# M7104B.net
KiCad netlist of a schematic drawn in EAGLE
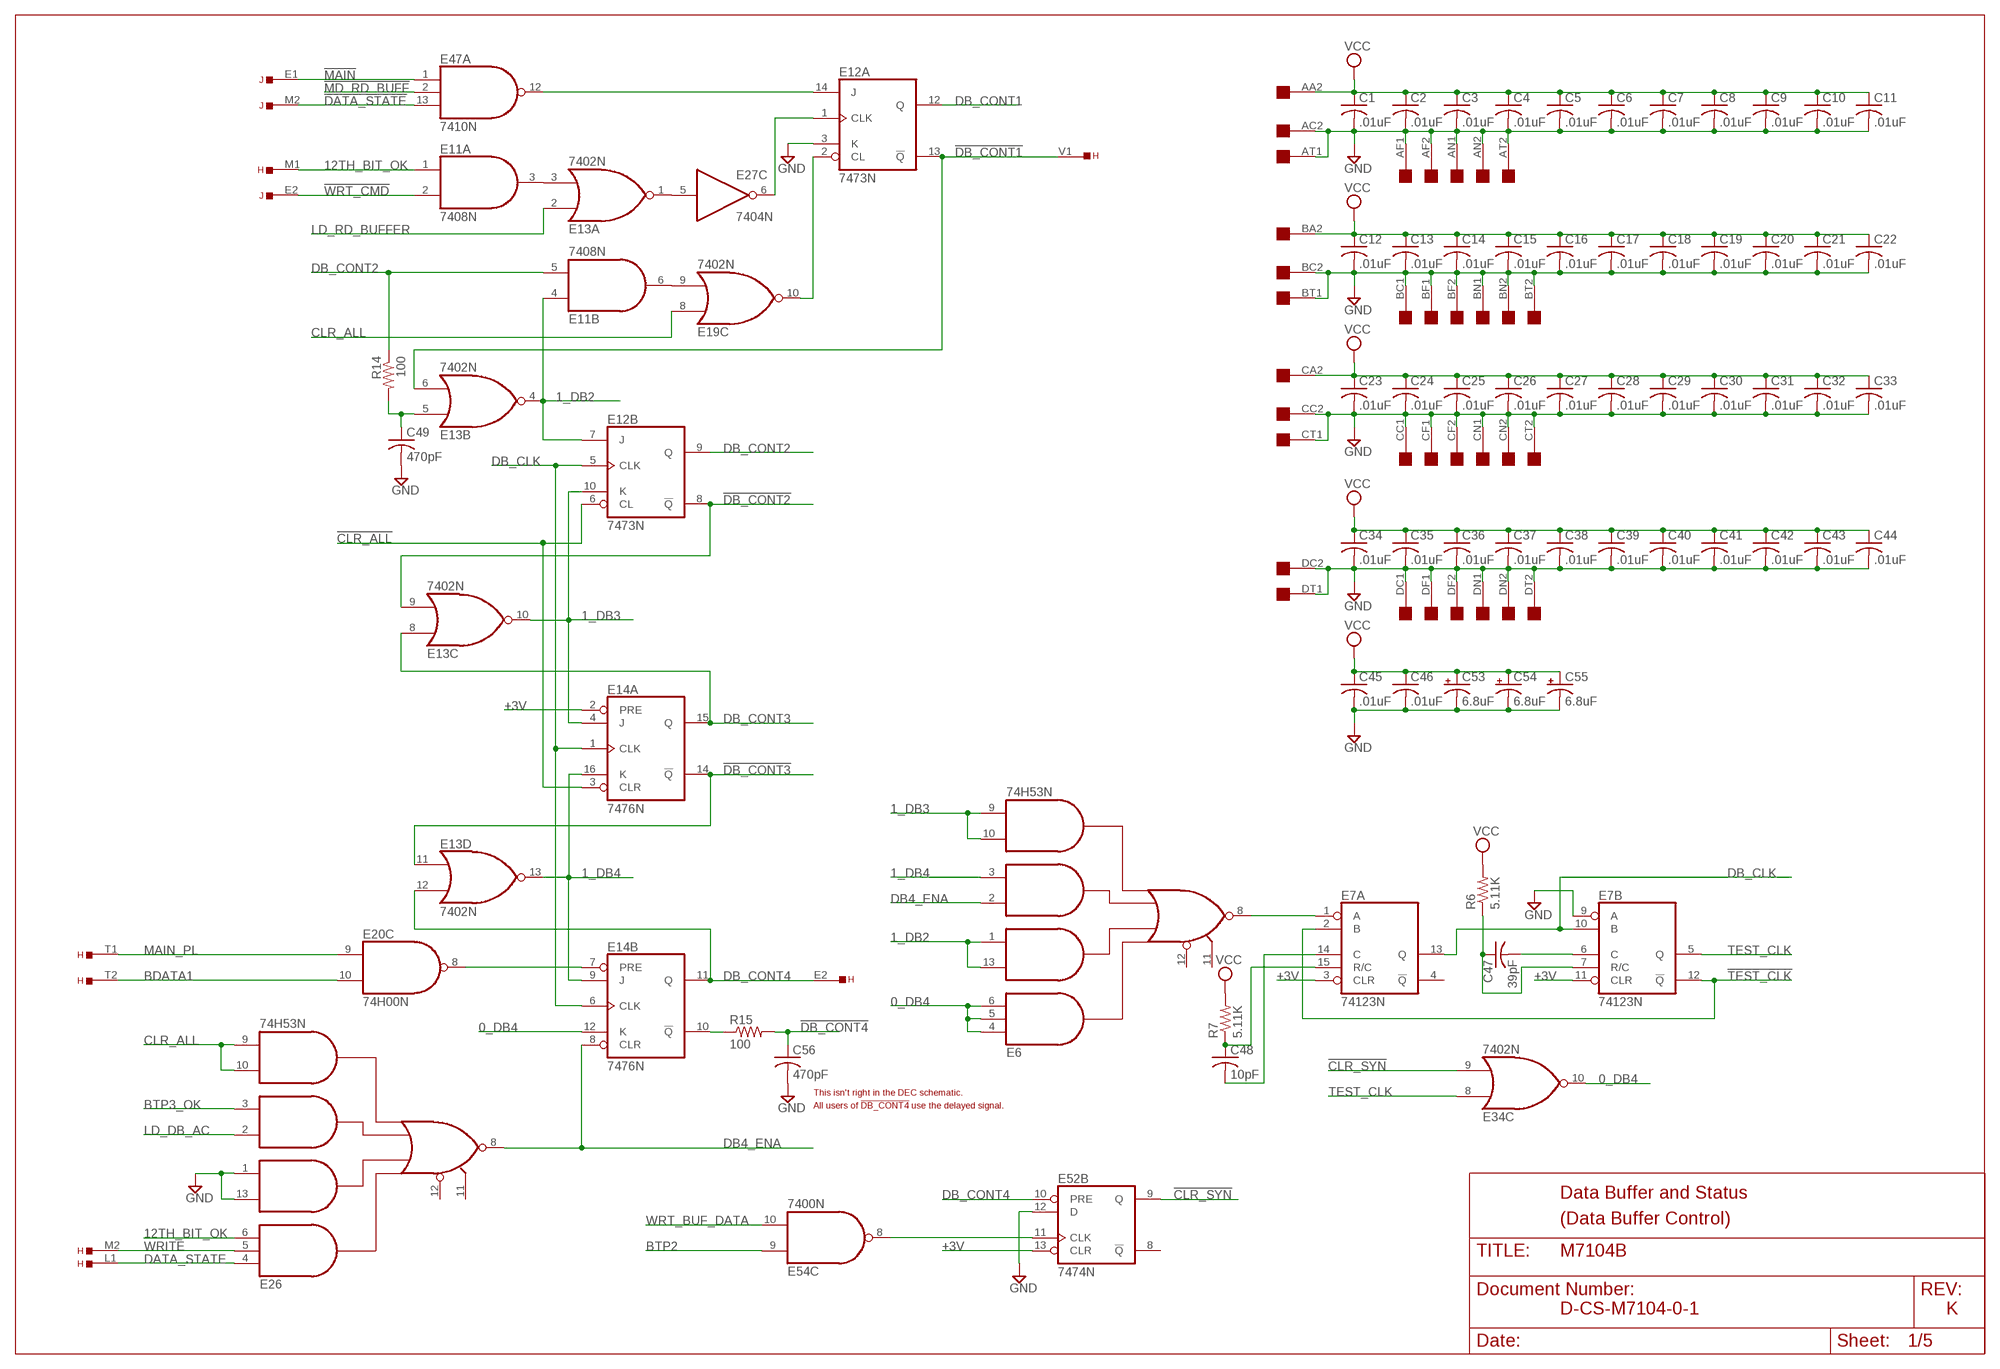
[diagram p0: schematic, sheet 1]
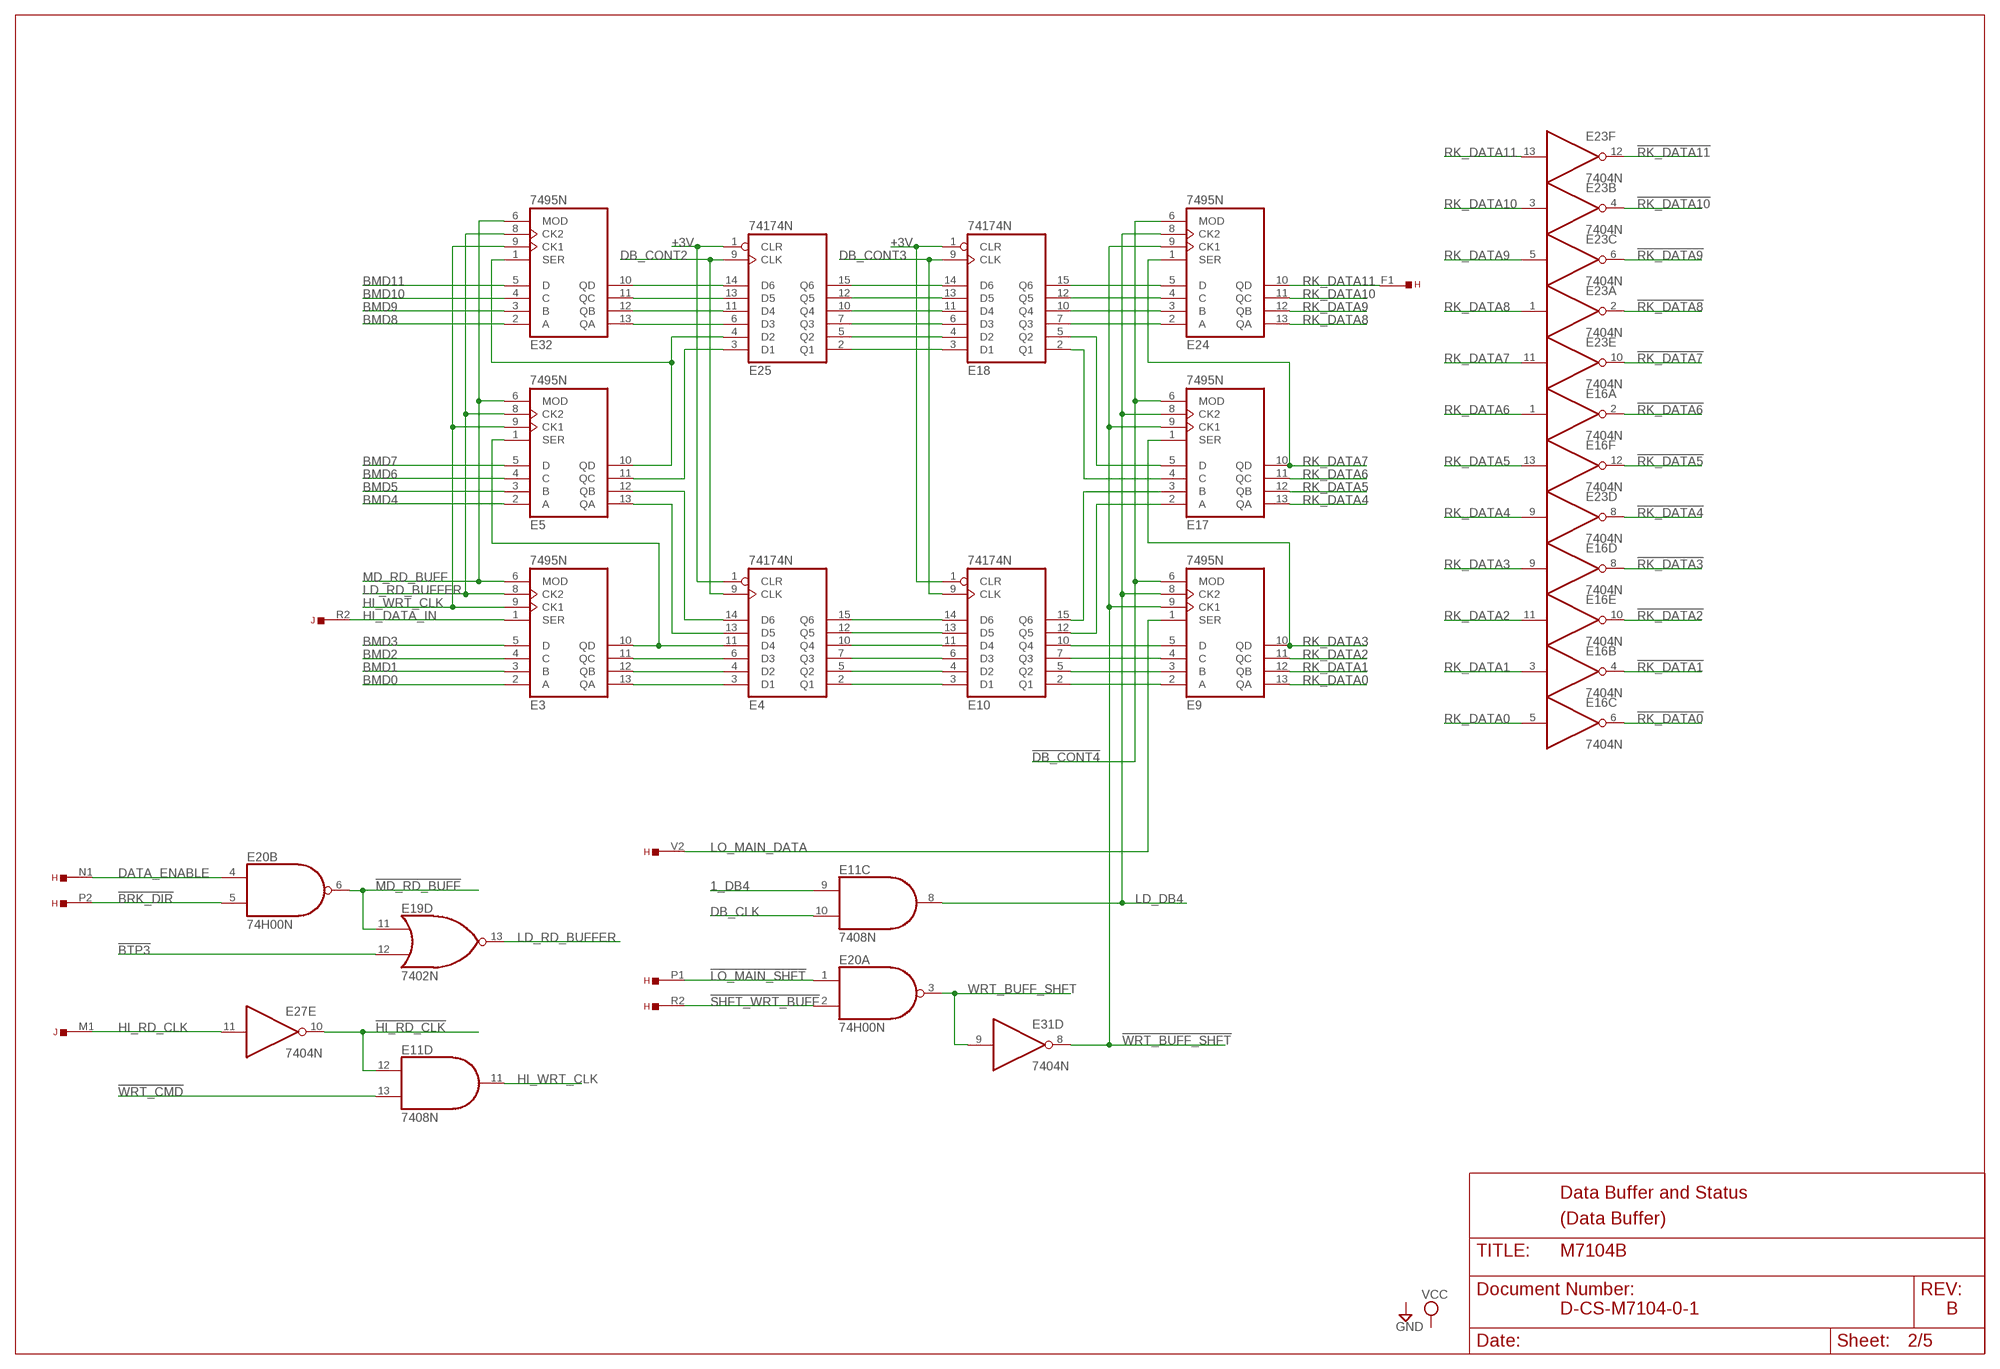
[diagram p1: schematic, sheet 2]
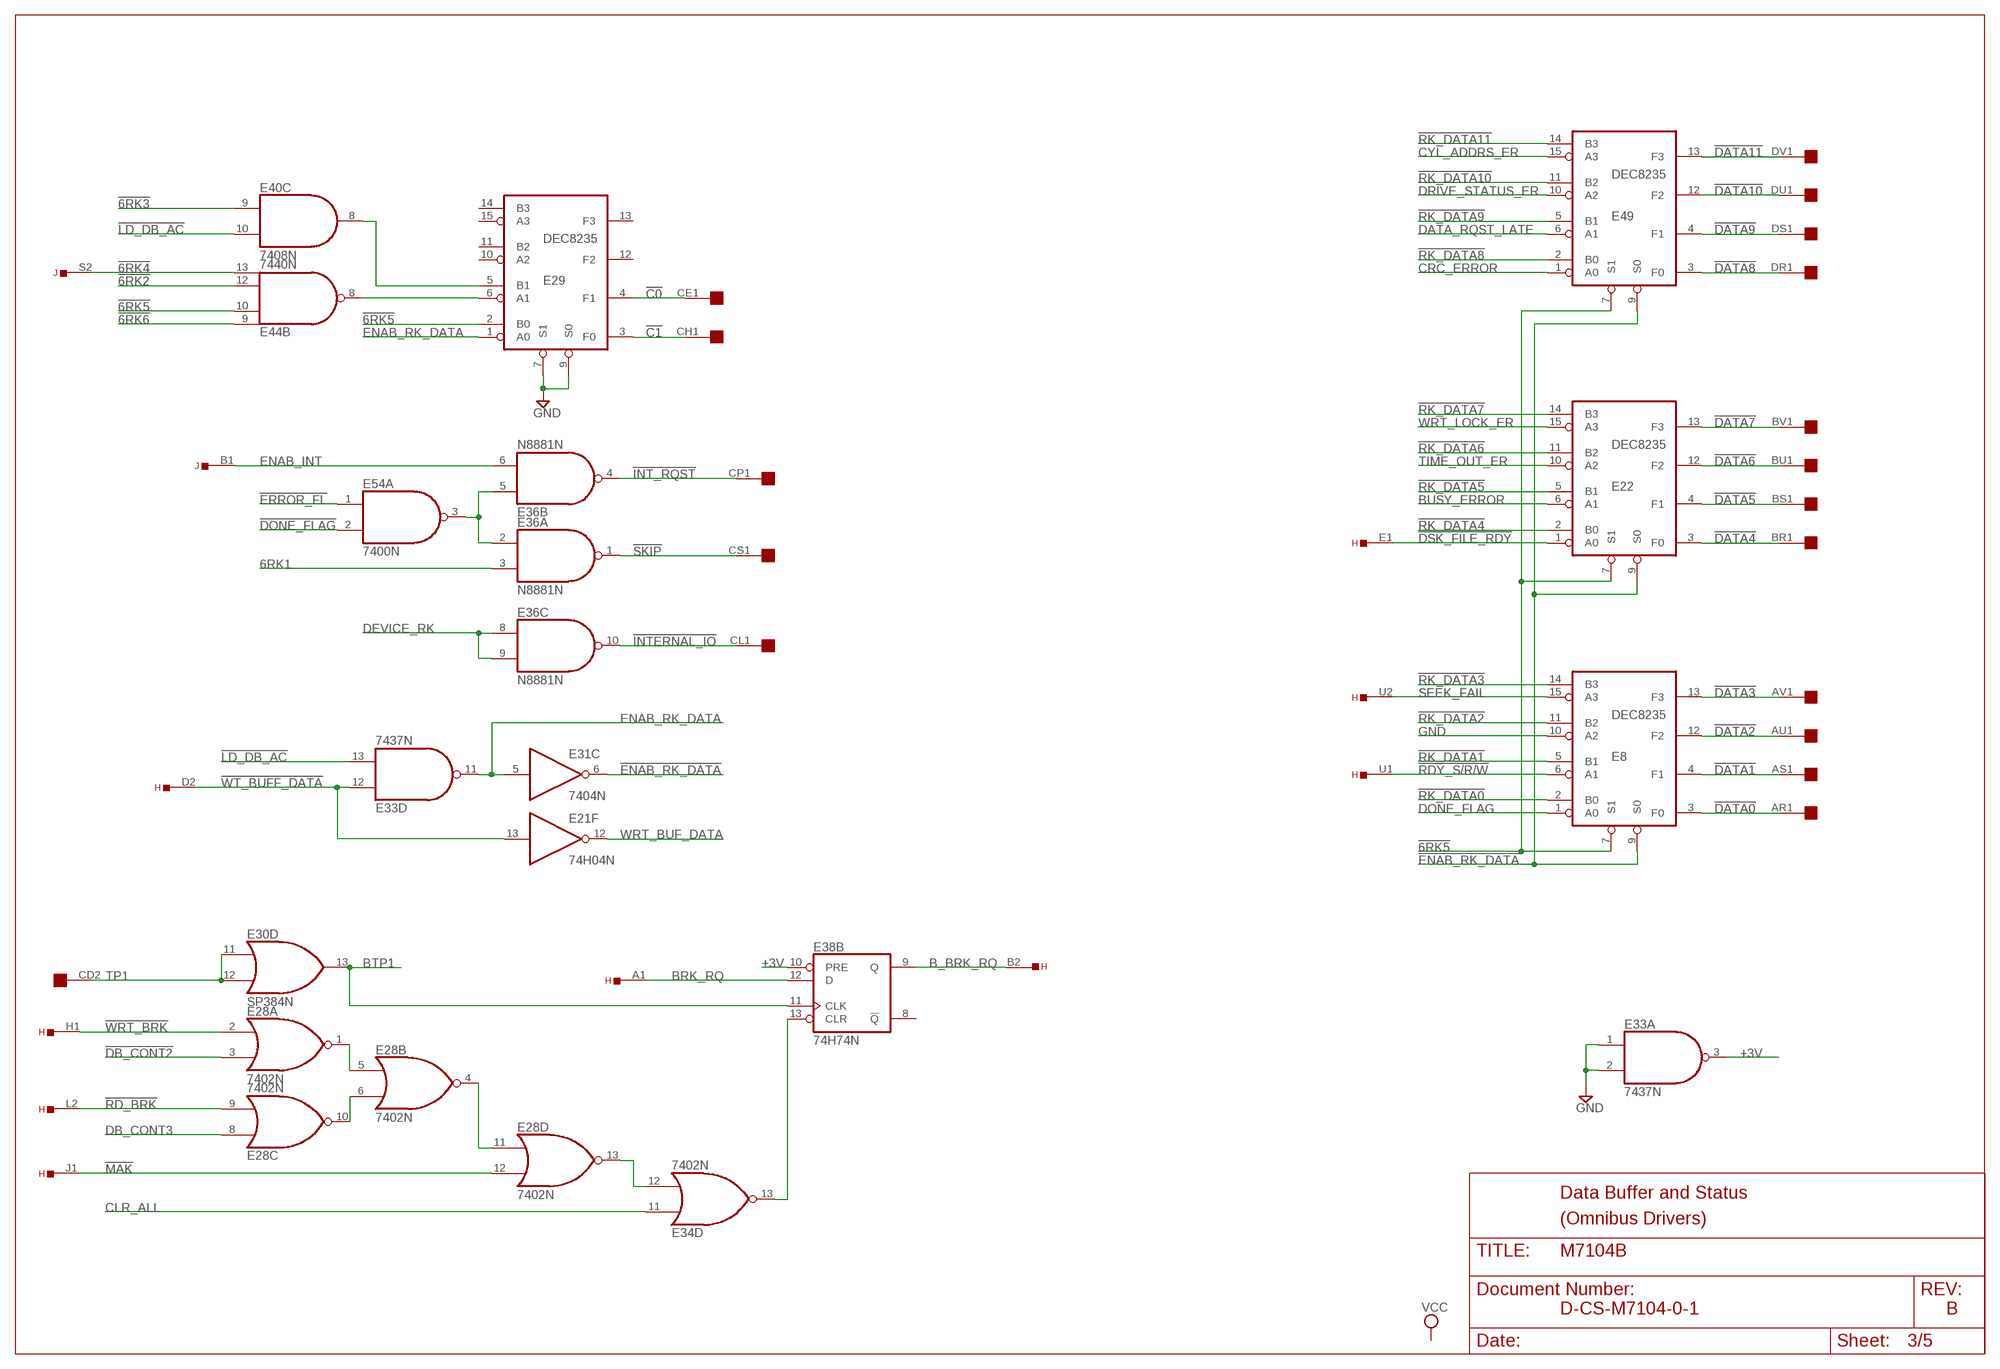
[diagram p2: schematic, sheet 3]
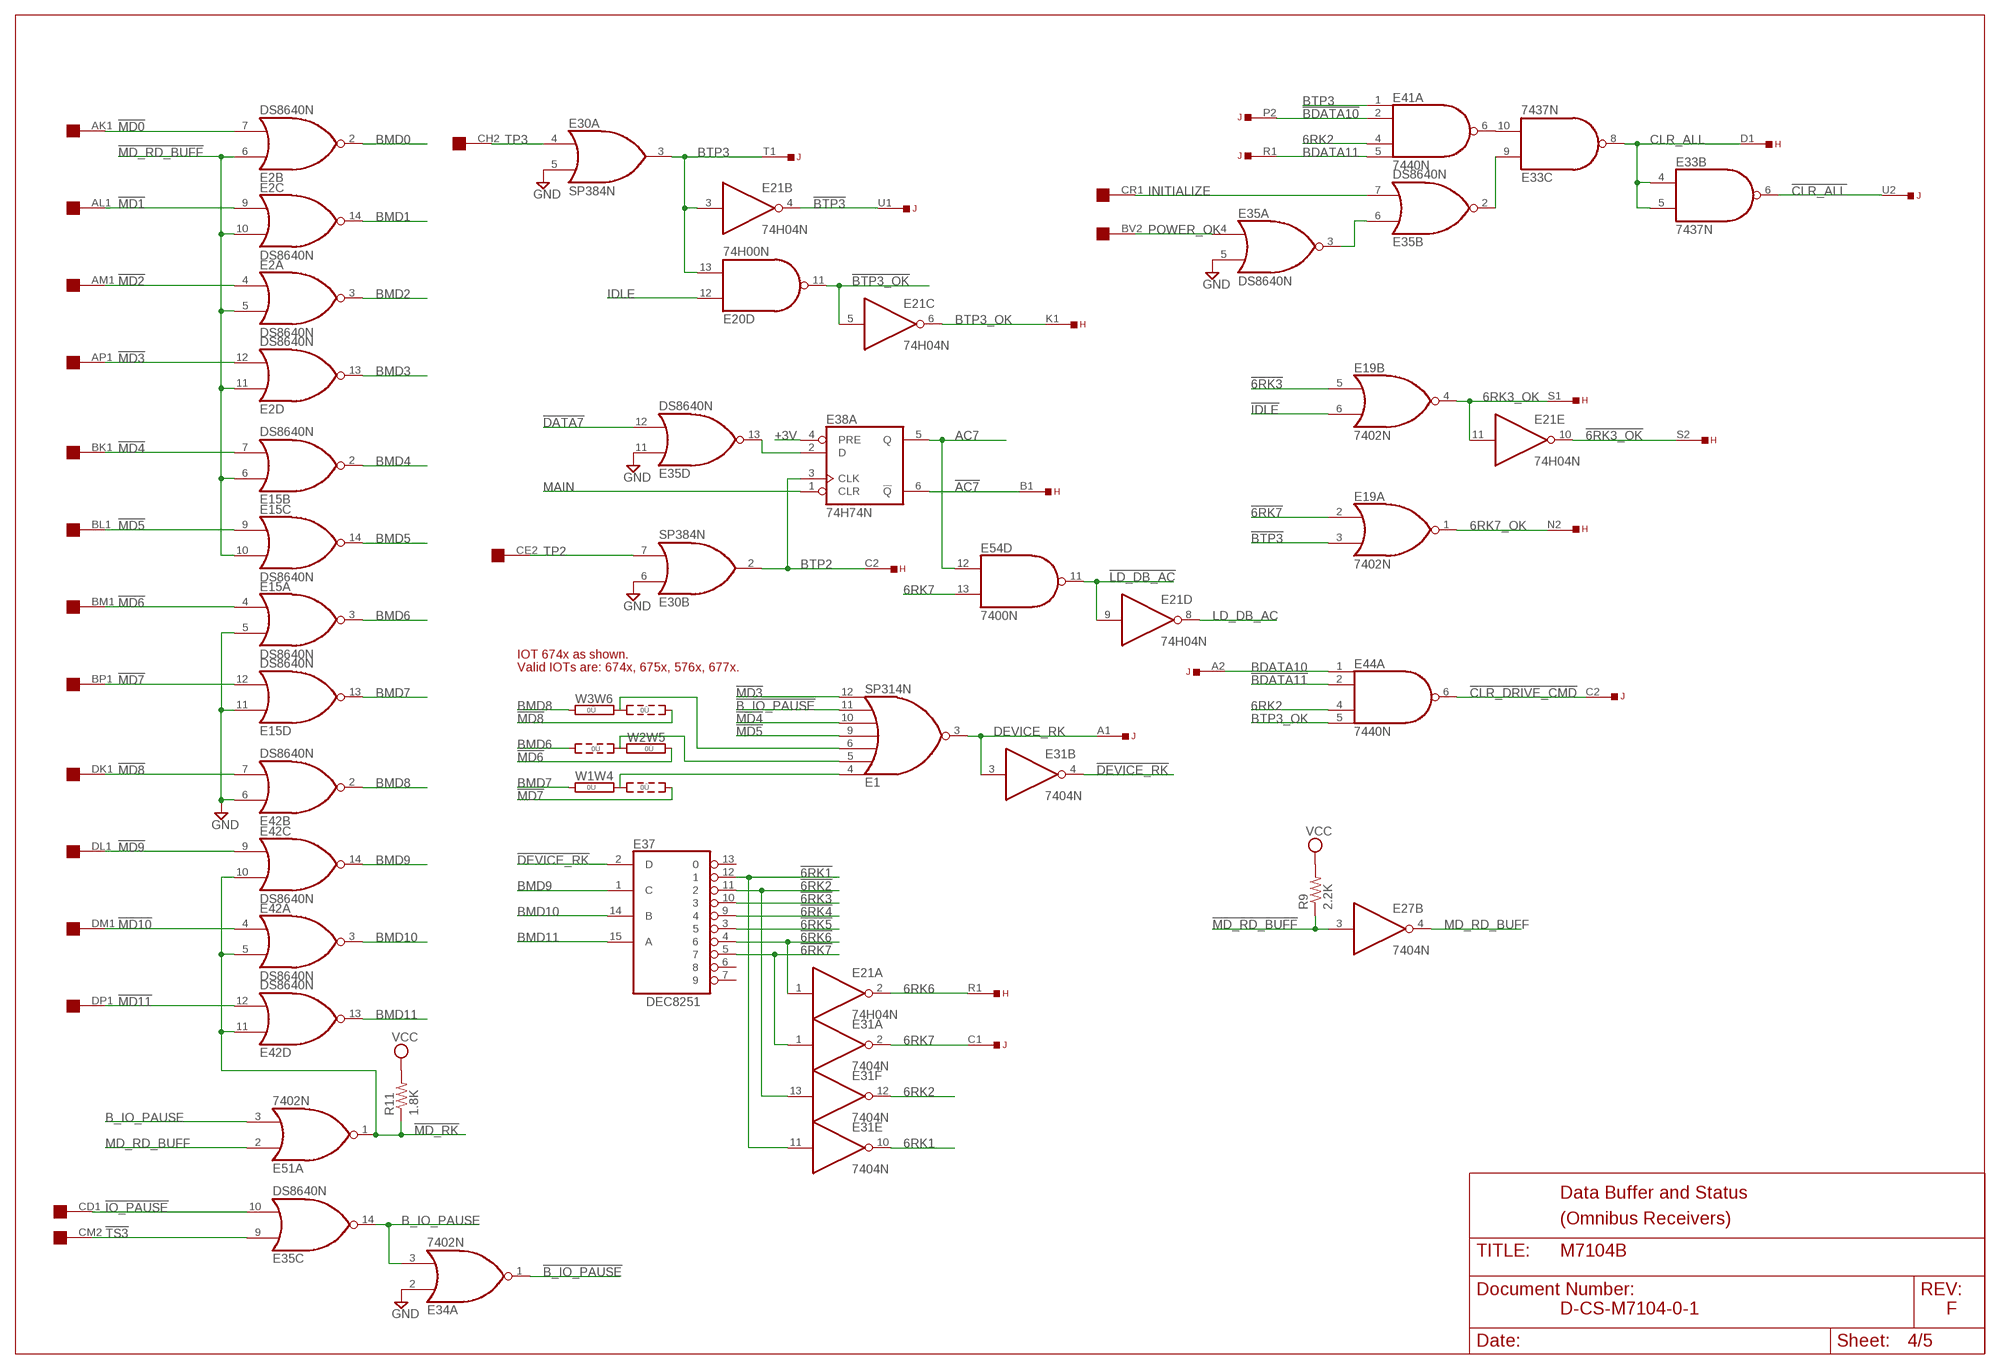
[diagram p3: schematic, sheet 4]
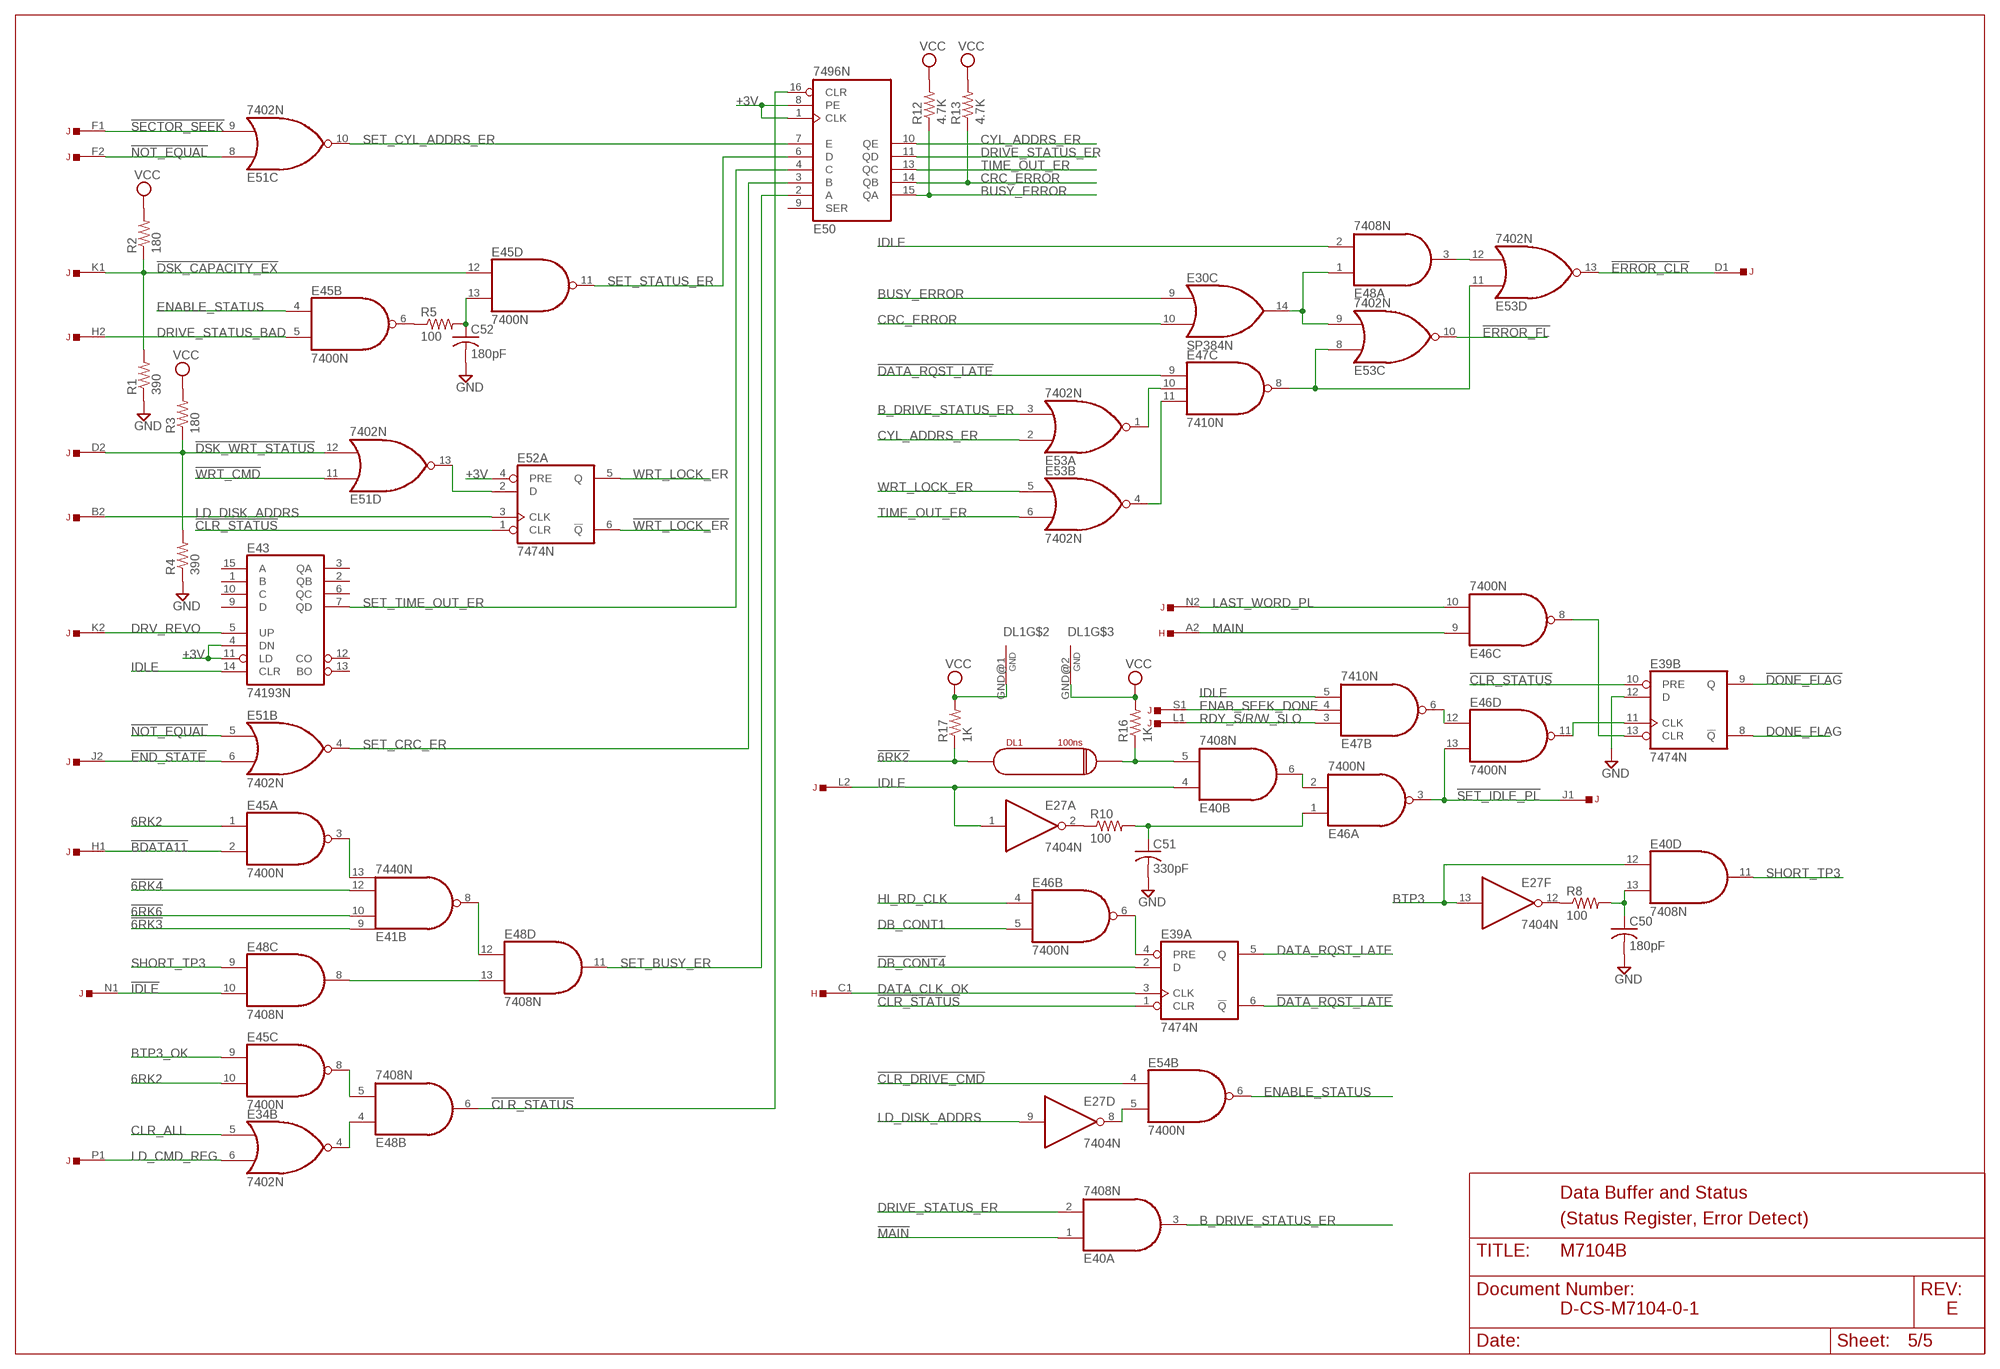
[diagram p4: schematic, sheet 5]

(export (version "E")
  (design (tool "Eeschema 10.0.6"))
  (components
    (comp (ref "E8")
      (value "DEC8235")
      (footprint "eagle-import:DIL16")
      (libsource (lib "eagle-import") (part "DEC8235"))
    )
    (comp (ref "E21")
      (value "74H04N")
      (footprint "eagle-import:DIL14")
      (libsource (lib "eagle-import") (part "7404N"))
    )
    (comp (ref "E22")
      (value "DEC8235")
      (footprint "eagle-import:DIL16")
      (libsource (lib "eagle-import") (part "DEC8235"))
    )
    (comp (ref "E28")
      (value "7402N")
      (footprint "eagle-import:DIL14")
      (libsource (lib "eagle-import") (part "7402N"))
    )
    (comp (ref "E29")
      (value "DEC8235")
      (footprint "eagle-import:DIL16")
      (libsource (lib "eagle-import") (part "DEC8235"))
    )
    (comp (ref "E30")
      (value "SP384N")
      (footprint "eagle-import:DIL14")
      (libsource (lib "eagle-import") (part "SP384N"))
    )
    (comp (ref "E31")
      (value "7404N")
      (footprint "eagle-import:DIL14")
      (libsource (lib "eagle-import") (part "7404N"))
    )
    (comp (ref "E33")
      (value "7437N")
      (footprint "eagle-import:DIL14")
      (libsource (lib "eagle-import") (part "7437N"))
    )
    (comp (ref "E34")
      (value "7402N")
      (footprint "eagle-import:DIL14")
      (libsource (lib "eagle-import") (part "7402N"))
    )
    (comp (ref "E36")
      (value "N8881N")
      (footprint "eagle-import:DIL14")
      (libsource (lib "eagle-import") (part "N8881N"))
    )
    (comp (ref "E38")
      (value "74H74N")
      (footprint "eagle-import:DIL14")
      (libsource (lib "eagle-import") (part "7474NS"))
    )
    (comp (ref "E40")
      (value "7408N")
      (footprint "eagle-import:DIL14")
      (libsource (lib "eagle-import") (part "7408NS"))
    )
    (comp (ref "E44")
      (value "7440N")
      (footprint "eagle-import:DIL14")
      (libsource (lib "eagle-import") (part "7440N"))
    )
    (comp (ref "E49")
      (value "DEC8235")
      (footprint "eagle-import:DIL16")
      (libsource (lib "eagle-import") (part "DEC8235"))
    )
    (comp (ref "E54")
      (value "7400N")
      (footprint "eagle-import:DIL14")
      (libsource (lib "eagle-import") (part "7400N"))
    )
    (comp (ref "H")
      (value "EDGE-TOP")
      (footprint "eagle-import:EDGE-CON2")
      (libsource (lib "eagle-import") (part "EDGE-TOP"))
    )
    (comp (ref "J")
      (value "EDGE-TOP")
      (footprint "eagle-import:EDGE-CON2")
      (libsource (lib "eagle-import") (part "EDGE-TOP"))
    )
    (comp (ref "OMNIBUS")
      (value "QUAD")
      (footprint "eagle-import:EDGE-CON8")
      (libsource (lib "eagle-import") (part "QUAD"))
    )
    (comp (ref "E3")
      (value "7495N")
      (footprint "eagle-import:DIL14")
      (libsource (lib "eagle-import") (part "7495N"))
    )
    (comp (ref "E4")
      (value "74174N")
      (footprint "eagle-import:DIL16")
      (libsource (lib "eagle-import") (part "74174N"))
    )
    (comp (ref "E5")
      (value "7495N")
      (footprint "eagle-import:DIL14")
      (libsource (lib "eagle-import") (part "7495N"))
    )
    (comp (ref "E9")
      (value "7495N")
      (footprint "eagle-import:DIL14")
      (libsource (lib "eagle-import") (part "7495N"))
    )
    (comp (ref "E10")
      (value "74174N")
      (footprint "eagle-import:DIL16")
      (libsource (lib "eagle-import") (part "74174N"))
    )
    (comp (ref "E11")
      (value "7408N")
      (footprint "eagle-import:DIL14")
      (libsource (lib "eagle-import") (part "7408NS"))
    )
    (comp (ref "E16")
      (value "7404N")
      (footprint "eagle-import:DIL14")
      (libsource (lib "eagle-import") (part "7404N"))
    )
    (comp (ref "E17")
      (value "7495N")
      (footprint "eagle-import:DIL14")
      (libsource (lib "eagle-import") (part "7495N"))
    )
    (comp (ref "E18")
      (value "74174N")
      (footprint "eagle-import:DIL16")
      (libsource (lib "eagle-import") (part "74174N"))
    )
    (comp (ref "E19")
      (value "7402N")
      (footprint "eagle-import:DIL14")
      (libsource (lib "eagle-import") (part "7402N"))
    )
    (comp (ref "E20")
      (value "74H00N")
      (footprint "eagle-import:DIL14")
      (libsource (lib "eagle-import") (part "7400NS"))
    )
    (comp (ref "E23")
      (value "7404N")
      (footprint "eagle-import:DIL14")
      (libsource (lib "eagle-import") (part "7404N"))
    )
    (comp (ref "E24")
      (value "7495N")
      (footprint "eagle-import:DIL14")
      (libsource (lib "eagle-import") (part "7495N"))
    )
    (comp (ref "E25")
      (value "74174N")
      (footprint "eagle-import:DIL16")
      (libsource (lib "eagle-import") (part "74174N"))
    )
    (comp (ref "E27")
      (value "7404N")
      (footprint "eagle-import:DIL14")
      (libsource (lib "eagle-import") (part "7404N"))
    )
    (comp (ref "E32")
      (value "7495N")
      (footprint "eagle-import:DIL14")
      (libsource (lib "eagle-import") (part "7495N"))
    )
    (comp (ref "E1")
      (value "SP314N")
      (footprint "eagle-import:DIL14")
      (libsource (lib "eagle-import") (part "SP314N"))
    )
    (comp (ref "E2")
      (value "DS8640N")
      (footprint "eagle-import:DIL14")
      (libsource (lib "eagle-import") (part "DS8640N"))
    )
    (comp (ref "E15")
      (value "DS8640N")
      (footprint "eagle-import:DIL14")
      (libsource (lib "eagle-import") (part "DS8640N"))
    )
    (comp (ref "E35")
      (value "DS8640N")
      (footprint "eagle-import:DIL14")
      (libsource (lib "eagle-import") (part "DS8640N"))
    )
    (comp (ref "E37")
      (value "DEC8251")
      (footprint "eagle-import:DIL16")
      (libsource (lib "eagle-import") (part "DEC8251"))
    )
    (comp (ref "E41")
      (value "7440N")
      (footprint "eagle-import:DIL14")
      (libsource (lib "eagle-import") (part "7440N"))
    )
    (comp (ref "E42")
      (value "DS8640N")
      (footprint "eagle-import:DIL14")
      (libsource (lib "eagle-import") (part "DS8640N"))
    )
    (comp (ref "E51")
      (value "7402N")
      (footprint "eagle-import:DIL14")
      (libsource (lib "eagle-import") (part "7402N"))
    )
    (comp (ref "R9")
      (value "2.2K")
      (footprint "eagle-import:0207_10")
      (libsource (lib "eagle-import") (part "R-US_0207/10"))
    )
    (comp (ref "R11")
      (value "1.8K")
      (footprint "eagle-import:0207_10")
      (libsource (lib "eagle-import") (part "R-US_0207/10"))
    )
    (comp (ref "W1W4")
      (value "0R2")
      (footprint "eagle-import:0R2_10")
      (libsource (lib "eagle-import") (part "0R2"))
    )
    (comp (ref "W2W5")
      (value "0R2")
      (footprint "eagle-import:0R2_10")
      (libsource (lib "eagle-import") (part "0R2"))
    )
    (comp (ref "W3W6")
      (value "0R2")
      (footprint "eagle-import:0R2_10")
      (libsource (lib "eagle-import") (part "0R2"))
    )
    (comp (ref "C1")
      (value ".01uF")
      (footprint "eagle-import:C063-025X075")
      (libsource (lib "eagle-import") (part "C-US"))
    )
    (comp (ref "C2")
      (value ".01uF")
      (footprint "eagle-import:C063-025X075")
      (libsource (lib "eagle-import") (part "C-US"))
    )
    (comp (ref "C3")
      (value ".01uF")
      (footprint "eagle-import:C063-025X075")
      (libsource (lib "eagle-import") (part "C-US"))
    )
    (comp (ref "C4")
      (value ".01uF")
      (footprint "eagle-import:C063-025X075")
      (libsource (lib "eagle-import") (part "C-US"))
    )
    (comp (ref "C5")
      (value ".01uF")
      (footprint "eagle-import:C063-025X075")
      (libsource (lib "eagle-import") (part "C-US"))
    )
    (comp (ref "C6")
      (value ".01uF")
      (footprint "eagle-import:C063-025X075")
      (libsource (lib "eagle-import") (part "C-US"))
    )
    (comp (ref "C7")
      (value ".01uF")
      (footprint "eagle-import:C063-025X075")
      (libsource (lib "eagle-import") (part "C-US"))
    )
    (comp (ref "C8")
      (value ".01uF")
      (footprint "eagle-import:C063-025X075")
      (libsource (lib "eagle-import") (part "C-US"))
    )
    (comp (ref "C9")
      (value ".01uF")
      (footprint "eagle-import:C063-025X075")
      (libsource (lib "eagle-import") (part "C-US"))
    )
    (comp (ref "C10")
      (value ".01uF")
      (footprint "eagle-import:C063-025X075")
      (libsource (lib "eagle-import") (part "C-US"))
    )
    (comp (ref "C11")
      (value ".01uF")
      (footprint "eagle-import:C063-025X075")
      (libsource (lib "eagle-import") (part "C-US"))
    )
    (comp (ref "C12")
      (value ".01uF")
      (footprint "eagle-import:C063-025X075")
      (libsource (lib "eagle-import") (part "C-US"))
    )
    (comp (ref "C13")
      (value ".01uF")
      (footprint "eagle-import:C063-025X075")
      (libsource (lib "eagle-import") (part "C-US"))
    )
    (comp (ref "C14")
      (value ".01uF")
      (footprint "eagle-import:C063-025X075")
      (libsource (lib "eagle-import") (part "C-US"))
    )
    (comp (ref "C15")
      (value ".01uF")
      (footprint "eagle-import:C063-025X075")
      (libsource (lib "eagle-import") (part "C-US"))
    )
    (comp (ref "C16")
      (value ".01uF")
      (footprint "eagle-import:C063-025X075")
      (libsource (lib "eagle-import") (part "C-US"))
    )
    (comp (ref "C17")
      (value ".01uF")
      (footprint "eagle-import:C063-025X075")
      (libsource (lib "eagle-import") (part "C-US"))
    )
    (comp (ref "C18")
      (value ".01uF")
      (footprint "eagle-import:C063-025X075")
      (libsource (lib "eagle-import") (part "C-US"))
    )
    (comp (ref "C19")
      (value ".01uF")
      (footprint "eagle-import:C063-025X075")
      (libsource (lib "eagle-import") (part "C-US"))
    )
    (comp (ref "C20")
      (value ".01uF")
      (footprint "eagle-import:C063-025X075")
      (libsource (lib "eagle-import") (part "C-US"))
    )
    (comp (ref "C21")
      (value ".01uF")
      (footprint "eagle-import:C063-025X075")
      (libsource (lib "eagle-import") (part "C-US"))
    )
    (comp (ref "C22")
      (value ".01uF")
      (footprint "eagle-import:C063-025X075")
      (libsource (lib "eagle-import") (part "C-US"))
    )
    (comp (ref "C23")
      (value ".01uF")
      (footprint "eagle-import:C063-025X075")
      (libsource (lib "eagle-import") (part "C-US"))
    )
    (comp (ref "C24")
      (value ".01uF")
      (footprint "eagle-import:C063-025X075")
      (libsource (lib "eagle-import") (part "C-US"))
    )
    (comp (ref "C25")
      (value ".01uF")
      (footprint "eagle-import:C063-025X075")
      (libsource (lib "eagle-import") (part "C-US"))
    )
    (comp (ref "C26")
      (value ".01uF")
      (footprint "eagle-import:C063-025X075")
      (libsource (lib "eagle-import") (part "C-US"))
    )
    (comp (ref "C27")
      (value ".01uF")
      (footprint "eagle-import:C063-025X075")
      (libsource (lib "eagle-import") (part "C-US"))
    )
    (comp (ref "C28")
      (value ".01uF")
      (footprint "eagle-import:C063-025X075")
      (libsource (lib "eagle-import") (part "C-US"))
    )
    (comp (ref "C29")
      (value ".01uF")
      (footprint "eagle-import:C063-025X075")
      (libsource (lib "eagle-import") (part "C-US"))
    )
    (comp (ref "C30")
      (value ".01uF")
      (footprint "eagle-import:C063-025X075")
      (libsource (lib "eagle-import") (part "C-US"))
    )
    (comp (ref "C31")
      (value ".01uF")
      (footprint "eagle-import:C063-025X075")
      (libsource (lib "eagle-import") (part "C-US"))
    )
    (comp (ref "C32")
      (value ".01uF")
      (footprint "eagle-import:C063-025X075")
      (libsource (lib "eagle-import") (part "C-US"))
    )
    (comp (ref "C33")
      (value ".01uF")
      (footprint "eagle-import:C063-025X075")
      (libsource (lib "eagle-import") (part "C-US"))
    )
    (comp (ref "C34")
      (value ".01uF")
      (footprint "eagle-import:C063-025X075")
      (libsource (lib "eagle-import") (part "C-US"))
    )
    (comp (ref "C35")
      (value ".01uF")
      (footprint "eagle-import:C063-025X075")
      (libsource (lib "eagle-import") (part "C-US"))
    )
    (comp (ref "C36")
      (value ".01uF")
      (footprint "eagle-import:C063-025X075")
      (libsource (lib "eagle-import") (part "C-US"))
    )
    (comp (ref "C37")
      (value ".01uF")
      (footprint "eagle-import:C063-025X075")
      (libsource (lib "eagle-import") (part "C-US"))
    )
    (comp (ref "C38")
      (value ".01uF")
      (footprint "eagle-import:C063-025X075")
      (libsource (lib "eagle-import") (part "C-US"))
    )
    (comp (ref "C39")
      (value ".01uF")
      (footprint "eagle-import:C063-025X075")
      (libsource (lib "eagle-import") (part "C-US"))
    )
    (comp (ref "C40")
      (value ".01uF")
      (footprint "eagle-import:C063-025X075")
      (libsource (lib "eagle-import") (part "C-US"))
    )
    (comp (ref "C41")
      (value ".01uF")
      (footprint "eagle-import:C063-025X075")
      (libsource (lib "eagle-import") (part "C-US"))
    )
    (comp (ref "C42")
      (value ".01uF")
      (footprint "eagle-import:C063-025X075")
      (libsource (lib "eagle-import") (part "C-US"))
    )
    (comp (ref "C43")
      (value ".01uF")
      (footprint "eagle-import:C063-025X075")
      (libsource (lib "eagle-import") (part "C-US"))
    )
    (comp (ref "C44")
      (value ".01uF")
      (footprint "eagle-import:C063-025X075")
      (libsource (lib "eagle-import") (part "C-US"))
    )
    (comp (ref "C45")
      (value ".01uF")
      (footprint "eagle-import:C063-025X075")
      (libsource (lib "eagle-import") (part "C-US"))
    )
    (comp (ref "C46")
      (value ".01uF")
      (footprint "eagle-import:C063-025X075")
      (libsource (lib "eagle-import") (part "C-US"))
    )
    (comp (ref "C47")
      (value "39pF")
      (footprint "eagle-import:C063-025X075")
      (libsource (lib "eagle-import") (part "C-US"))
    )
    (comp (ref "C48")
      (value "10pF")
      (footprint "eagle-import:C063-025X075")
      (libsource (lib "eagle-import") (part "C-US"))
    )
    (comp (ref "C49")
      (value "470pF")
      (footprint "eagle-import:C063-025X075")
      (libsource (lib "eagle-import") (part "C-US"))
    )
    (comp (ref "C53")
      (value "6.8uF")
      (footprint "eagle-import:E12-8")
      (libsource (lib "eagle-import") (part "CPOL-USE20-8AXIAL"))
    )
    (comp (ref "C54")
      (value "6.8uF")
      (footprint "eagle-import:E12-8")
      (libsource (lib "eagle-import") (part "CPOL-USE20-8AXIAL"))
    )
    (comp (ref "C55")
      (value "6.8uF")
      (footprint "eagle-import:E12-8")
      (libsource (lib "eagle-import") (part "CPOL-USE20-8AXIAL"))
    )
    (comp (ref "C56")
      (value "470pF")
      (footprint "eagle-import:C063-025X075")
      (libsource (lib "eagle-import") (part "C-US"))
    )
    (comp (ref "E6")
      (value "74H53N")
      (footprint "eagle-import:DIL14")
      (libsource (lib "eagle-import") (part "74H53N"))
    )
    (comp (ref "E7")
      (value "74123N")
      (footprint "eagle-import:DIL16")
      (libsource (lib "eagle-import") (part "74123N"))
    )
    (comp (ref "E12")
      (value "7473N")
      (footprint "eagle-import:DIL14")
      (libsource (lib "eagle-import") (part "7473NLS"))
    )
    (comp (ref "E13")
      (value "7402N")
      (footprint "eagle-import:DIL14")
      (libsource (lib "eagle-import") (part "7402N"))
    )
    (comp (ref "E14")
      (value "7476N")
      (footprint "eagle-import:DIL16")
      (libsource (lib "eagle-import") (part "7476N"))
    )
    (comp (ref "E26")
      (value "74H53N")
      (footprint "eagle-import:DIL14")
      (libsource (lib "eagle-import") (part "74H53N"))
    )
    (comp (ref "E47")
      (value "7410N")
      (footprint "eagle-import:DIL14")
      (libsource (lib "eagle-import") (part "7410N"))
    )
    (comp (ref "E52")
      (value "7474N")
      (footprint "eagle-import:DIL14")
      (libsource (lib "eagle-import") (part "7474NS"))
    )
    (comp (ref "R6")
      (value "5.11K")
      (footprint "eagle-import:0207_15")
      (libsource (lib "eagle-import") (part "R-US_0207/15"))
    )
    (comp (ref "R7")
      (value "5.11K")
      (footprint "eagle-import:0207_15")
      (libsource (lib "eagle-import") (part "R-US_0207/15"))
    )
    (comp (ref "R14")
      (value "100")
      (footprint "eagle-import:0207_10")
      (libsource (lib "eagle-import") (part "R-US_0207/10"))
    )
    (comp (ref "R15")
      (value "100")
      (footprint "eagle-import:0207_10")
      (libsource (lib "eagle-import") (part "R-US_0207/10"))
    )
    (comp (ref "C50")
      (value "180pF")
      (footprint "eagle-import:C063-025X075")
      (libsource (lib "eagle-import") (part "C-US"))
    )
    (comp (ref "C51")
      (value "330pF")
      (footprint "eagle-import:C063-025X075")
      (libsource (lib "eagle-import") (part "C-US"))
    )
    (comp (ref "C52")
      (value "180pF")
      (footprint "eagle-import:C063-025X075")
      (libsource (lib "eagle-import") (part "C-US"))
    )
    (comp (ref "DL1")
      (value "100ns")
      (footprint "eagle-import:RCL-L-XX-22")
      (libsource (lib "eagle-import") (part "RC-L-22"))
    )
    (comp (ref "E39")
      (value "7474N")
      (footprint "eagle-import:DIL14")
      (libsource (lib "eagle-import") (part "7474NS"))
    )
    (comp (ref "E43")
      (value "74193N")
      (footprint "eagle-import:DIL16")
      (libsource (lib "eagle-import") (part "74193N"))
    )
    (comp (ref "E45")
      (value "7400N")
      (footprint "eagle-import:DIL14")
      (libsource (lib "eagle-import") (part "7400N"))
    )
    (comp (ref "E46")
      (value "7400N")
      (footprint "eagle-import:DIL14")
      (libsource (lib "eagle-import") (part "7400N"))
    )
    (comp (ref "E48")
      (value "7408N")
      (footprint "eagle-import:DIL14")
      (libsource (lib "eagle-import") (part "7408NS"))
    )
    (comp (ref "E50")
      (value "7496N")
      (footprint "eagle-import:DIL16")
      (libsource (lib "eagle-import") (part "7496NLS"))
    )
    (comp (ref "E53")
      (value "7402N")
      (footprint "eagle-import:DIL14")
      (libsource (lib "eagle-import") (part "7402N"))
    )
    (comp (ref "R1")
      (value "390")
      (footprint "eagle-import:0207_10")
      (libsource (lib "eagle-import") (part "R-US_0207/10"))
    )
    (comp (ref "R2")
      (value "180")
      (footprint "eagle-import:0207_10")
      (libsource (lib "eagle-import") (part "R-US_0207/10"))
    )
    (comp (ref "R3")
      (value "180")
      (footprint "eagle-import:0207_10")
      (libsource (lib "eagle-import") (part "R-US_0207/10"))
    )
    (comp (ref "R4")
      (value "390")
      (footprint "eagle-import:0207_10")
      (libsource (lib "eagle-import") (part "R-US_0207/10"))
    )
    (comp (ref "R5")
      (value "100")
      (footprint "eagle-import:0207_10")
      (libsource (lib "eagle-import") (part "R-US_0207/10"))
    )
    (comp (ref "R8")
      (value "100")
      (footprint "eagle-import:0207_10")
      (libsource (lib "eagle-import") (part "R-US_0207/10"))
    )
    (comp (ref "R10")
      (value "100")
      (footprint "eagle-import:0207_10")
      (libsource (lib "eagle-import") (part "R-US_0207/10"))
    )
    (comp (ref "R12")
      (value "4.7K")
      (footprint "eagle-import:0207_10")
      (libsource (lib "eagle-import") (part "R-US_0207/10"))
    )
    (comp (ref "R13")
      (value "4.7K")
      (footprint "eagle-import:0207_10")
      (libsource (lib "eagle-import") (part "R-US_0207/10"))
    )
    (comp (ref "R16")
      (value "1K")
      (footprint "eagle-import:0207_10")
      (libsource (lib "eagle-import") (part "R-US_0207/10"))
    )
    (comp (ref "R17")
      (value "1K")
      (footprint "eagle-import:0207_10")
      (libsource (lib "eagle-import") (part "R-US_0207/10"))
    )
  )
  (nets
    (net (code "1") (name "+3V") (class "Default")
      (node (ref "E10") (pin "1") (pinfunction "CLR_1") (pintype "input"))
      (node (ref "E14") (pin "2") (pinfunction "PRE_2") (pintype "input"))
      (node (ref "E18") (pin "1") (pinfunction "CLR_1") (pintype "input"))
      (node (ref "E25") (pin "1") (pinfunction "CLR_1") (pintype "input"))
      (node (ref "E33") (pin "3") (pinfunction "O_3") (pintype "output"))
      (node (ref "E38") (pin "10") (pinfunction "PRE_10") (pintype "input"))
      (node (ref "E38") (pin "4") (pinfunction "PRE_4") (pintype "input"))
      (node (ref "E4") (pin "1") (pinfunction "CLR_1") (pintype "input"))
      (node (ref "E43") (pin "11") (pinfunction "LD_11") (pintype "input"))
      (node (ref "E43") (pin "4") (pinfunction "DN_4") (pintype "input"))
      (node (ref "E50") (pin "1") (pinfunction "CLK_1") (pintype "input"))
      (node (ref "E50") (pin "8") (pinfunction "PE_8") (pintype "input"))
      (node (ref "E52") (pin "13") (pinfunction "CLR_13") (pintype "input"))
      (node (ref "E52") (pin "4") (pinfunction "PRE_4") (pintype "input"))
      (node (ref "E7") (pin "11") (pinfunction "CLR_11") (pintype "input"))
      (node (ref "E7") (pin "3") (pinfunction "CLR_3") (pintype "input"))
    )
    (net (code "2") (name "0_DB4") (class "Default")
      (node (ref "E14") (pin "12") (pinfunction "K_12") (pintype "input"))
      (node (ref "E34") (pin "10") (pinfunction "O_10") (pintype "output"))
      (node (ref "E6") (pin "4") (pinfunction "I1_4") (pintype "input"))
      (node (ref "E6") (pin "5") (pinfunction "I11_5") (pintype "input"))
      (node (ref "E6") (pin "6") (pinfunction "I2_6") (pintype "input"))
    )
    (net (code "3") (name "1_DB2") (class "Default")
      (node (ref "E11") (pin "4") (pinfunction "I0_4") (pintype "input"))
      (node (ref "E12") (pin "7") (pinfunction "J_7") (pintype "input"))
      (node (ref "E13") (pin "4") (pinfunction "O_4") (pintype "output"))
      (node (ref "E6") (pin "1") (pinfunction "I4_1") (pintype "input"))
      (node (ref "E6") (pin "13") (pinfunction "I3_13") (pintype "input"))
    )
    (net (code "4") (name "1_DB3") (class "Default")
      (node (ref "E12") (pin "10") (pinfunction "K_10") (pintype "input"))
      (node (ref "E13") (pin "10") (pinfunction "O_10") (pintype "output"))
      (node (ref "E14") (pin "4") (pinfunction "J_4") (pintype "input"))
      (node (ref "E6") (pin "10") (pinfunction "I7_10") (pintype "input"))
      (node (ref "E6") (pin "9") (pinfunction "I8_9") (pintype "input"))
    )
    (net (code "5") (name "1_DB4") (class "Default")
      (node (ref "E11") (pin "9") (pinfunction "I0_9") (pintype "input"))
      (node (ref "E13") (pin "13") (pinfunction "O_13") (pintype "output"))
      (node (ref "E14") (pin "16") (pinfunction "K_16") (pintype "input"))
      (node (ref "E14") (pin "9") (pinfunction "J_9") (pintype "input"))
      (node (ref "E6") (pin "3") (pinfunction "I6_3") (pintype "input"))
    )
    (net (code "6") (name "6RK1") (class "Default")
      (node (ref "E31") (pin "10") (pinfunction "O_10") (pintype "output"))
      (node (ref "E36") (pin "3") (pinfunction "I1_3") (pintype "input"))
    )
    (net (code "7") (name "6RK2") (class "Default")
      (node (ref "E31") (pin "12") (pinfunction "O_12") (pintype "output"))
      (node (ref "E41") (pin "4") (pinfunction "I2_4") (pintype "input"))
      (node (ref "E44") (pin "4") (pinfunction "I2_4") (pintype "input"))
      (node (ref "E45") (pin "1") (pinfunction "I0_1") (pintype "input"))
      (node (ref "E45") (pin "10") (pinfunction "I1_10") (pintype "input"))
    )
    (net (code "8") (name "6RK3_OK") (class "Default")
      (node (ref "E19") (pin "4") (pinfunction "O_4") (pintype "output"))
      (node (ref "E21") (pin "11") (pinfunction "I_11") (pintype "input"))
      (node (ref "H") (pin "S1") (pinfunction "P_S1") (pintype "passive"))
    )
    (net (code "9") (name "6RK6") (class "Default")
      (node (ref "E21") (pin "2") (pinfunction "O_2") (pintype "output"))
      (node (ref "H") (pin "R1") (pinfunction "P_R1") (pintype "passive"))
    )
    (net (code "10") (name "6RK7") (class "Default")
      (node (ref "E31") (pin "2") (pinfunction "O_2") (pintype "output"))
      (node (ref "E54") (pin "13") (pinfunction "I1_13") (pintype "input"))
      (node (ref "J") (pin "C1") (pinfunction "P_C1") (pintype "passive"))
    )
    (net (code "11") (name "6RK7_OK") (class "Default")
      (node (ref "E19") (pin "1") (pinfunction "O_1") (pintype "output"))
      (node (ref "H") (pin "N2") (pinfunction "P_N2") (pintype "passive"))
    )
    (net (code "12") (name "12TH_BIT_OK") (class "Default")
      (node (ref "E11") (pin "1") (pinfunction "I0_1") (pintype "input"))
      (node (ref "E26") (pin "6") (pinfunction "I2_6") (pintype "input"))
      (node (ref "H") (pin "M1") (pinfunction "P_M1") (pintype "passive"))
    )
    (net (code "13") (name "AC7") (class "Default")
      (node (ref "E38") (pin "5") (pinfunction "Q_5") (pintype "output"))
      (node (ref "E54") (pin "12") (pinfunction "I0_12") (pintype "input"))
    )
    (net (code "14") (name "BDATA1") (class "Default")
      (node (ref "E20") (pin "10") (pinfunction "I1_10") (pintype "input"))
      (node (ref "H") (pin "T2") (pinfunction "P_T2") (pintype "passive"))
    )
    (net (code "15") (name "BDATA10") (class "Default")
      (node (ref "E44") (pin "1") (pinfunction "I0_1") (pintype "input"))
      (node (ref "J") (pin "A2") (pinfunction "P_A2") (pintype "passive"))
    )
    (net (code "16") (name "BDATA11") (class "Default")
      (node (ref "E41") (pin "5") (pinfunction "I3_5") (pintype "input"))
      (node (ref "J") (pin "R1") (pinfunction "P_R1") (pintype "passive"))
    )
    (net (code "17") (name "BMD0") (class "Default")
      (node (ref "E2") (pin "2") (pinfunction "O_2") (pintype "output"))
      (node (ref "E3") (pin "2") (pinfunction "A_2") (pintype "input"))
    )
    (net (code "18") (name "BMD1") (class "Default")
      (node (ref "E2") (pin "14") (pinfunction "O_14") (pintype "output"))
      (node (ref "E3") (pin "3") (pinfunction "B_3") (pintype "input"))
    )
    (net (code "19") (name "BMD2") (class "Default")
      (node (ref "E2") (pin "3") (pinfunction "O_3") (pintype "output"))
      (node (ref "E3") (pin "4") (pinfunction "C_4") (pintype "input"))
    )
    (net (code "20") (name "BMD3") (class "Default")
      (node (ref "E2") (pin "13") (pinfunction "O_13") (pintype "output"))
      (node (ref "E3") (pin "5") (pinfunction "D_5") (pintype "input"))
    )
    (net (code "21") (name "BMD4") (class "Default")
      (node (ref "E15") (pin "2") (pinfunction "O_2") (pintype "output"))
      (node (ref "E5") (pin "2") (pinfunction "A_2") (pintype "input"))
    )
    (net (code "22") (name "BMD5") (class "Default")
      (node (ref "E15") (pin "14") (pinfunction "O_14") (pintype "output"))
      (node (ref "E5") (pin "3") (pinfunction "B_3") (pintype "input"))
    )
    (net (code "23") (name "BMD6") (class "Default")
      (node (ref "E15") (pin "3") (pinfunction "O_3") (pintype "output"))
      (node (ref "E5") (pin "4") (pinfunction "C_4") (pintype "input"))
      (node (ref "W2W5") (pin "3") (pinfunction "3_3") (pintype "passive"))
    )
    (net (code "24") (name "BMD7") (class "Default")
      (node (ref "E15") (pin "13") (pinfunction "O_13") (pintype "output"))
      (node (ref "E5") (pin "5") (pinfunction "D_5") (pintype "input"))
      (node (ref "W1W4") (pin "1") (pinfunction "1_1") (pintype "passive"))
    )
    (net (code "25") (name "BMD8") (class "Default")
      (node (ref "E32") (pin "2") (pinfunction "A_2") (pintype "input"))
      (node (ref "E42") (pin "2") (pinfunction "O_2") (pintype "output"))
      (node (ref "W3W6") (pin "1") (pinfunction "1_1") (pintype "passive"))
    )
    (net (code "26") (name "BMD9") (class "Default")
      (node (ref "E32") (pin "3") (pinfunction "B_3") (pintype "input"))
      (node (ref "E37") (pin "1") (pinfunction "C_1") (pintype "input"))
      (node (ref "E42") (pin "14") (pinfunction "O_14") (pintype "output"))
    )
    (net (code "27") (name "BMD10") (class "Default")
      (node (ref "E32") (pin "4") (pinfunction "C_4") (pintype "input"))
      (node (ref "E37") (pin "14") (pinfunction "B_14") (pintype "input"))
      (node (ref "E42") (pin "3") (pinfunction "O_3") (pintype "output"))
    )
    (net (code "28") (name "BMD11") (class "Default")
      (node (ref "E32") (pin "5") (pinfunction "D_5") (pintype "input"))
      (node (ref "E37") (pin "15") (pinfunction "A_15") (pintype "input"))
      (node (ref "E42") (pin "13") (pinfunction "O_13") (pintype "output"))
    )
    (net (code "29") (name "BRK_RQ") (class "Default")
      (node (ref "E38") (pin "12") (pinfunction "D_12") (pintype "input"))
      (node (ref "H") (pin "A1") (pinfunction "P_A1") (pintype "passive"))
    )
    (net (code "30") (name "BTP1") (class "Default")
      (node (ref "E30") (pin "13") (pinfunction "O_13") (pintype "output"))
      (node (ref "E38") (pin "11") (pinfunction "CLK_11") (pintype "input"))
    )
    (net (code "31") (name "BTP2") (class "Default")
      (node (ref "E30") (pin "2") (pinfunction "O_2") (pintype "output"))
      (node (ref "E38") (pin "3") (pinfunction "CLK_3") (pintype "input"))
      (node (ref "E54") (pin "9") (pinfunction "I0_9") (pintype "input"))
      (node (ref "H") (pin "C2") (pinfunction "P_C2") (pintype "passive"))
    )
    (net (code "32") (name "BTP3") (class "Default")
      (node (ref "E20") (pin "13") (pinfunction "I1_13") (pintype "input"))
      (node (ref "E21") (pin "3") (pinfunction "I_3") (pintype "input"))
      (node (ref "E27") (pin "13") (pinfunction "I_13") (pintype "input"))
      (node (ref "E30") (pin "3") (pinfunction "O_3") (pintype "output"))
      (node (ref "E40") (pin "12") (pinfunction "I0_12") (pintype "input"))
      (node (ref "E41") (pin "1") (pinfunction "I0_1") (pintype "input"))
      (node (ref "J") (pin "T1") (pinfunction "P_T1") (pintype "passive"))
    )
    (net (code "33") (name "BTP3_OK") (class "Default")
      (node (ref "E21") (pin "6") (pinfunction "O_6") (pintype "output"))
      (node (ref "E26") (pin "3") (pinfunction "I6_3") (pintype "input"))
      (node (ref "E44") (pin "5") (pinfunction "I3_5") (pintype "input"))
      (node (ref "E45") (pin "9") (pinfunction "I0_9") (pintype "input"))
      (node (ref "H") (pin "K1") (pinfunction "P_K1") (pintype "passive"))
    )
    (net (code "34") (name "BUSY_ERROR") (class "Default")
      (node (ref "E22") (pin "6") (pinfunction "A1_6") (pintype "input"))
      (node (ref "E30") (pin "9") (pinfunction "I0_9") (pintype "input"))
      (node (ref "E50") (pin "15") (pinfunction "QA_15") (pintype "output"))
      (node (ref "R12") (pin "1") (pinfunction "1_1") (pintype "passive"))
    )
    (net (code "35") (name "B_BRK_RQ") (class "Default")
      (node (ref "E38") (pin "9") (pinfunction "Q_9") (pintype "output"))
      (node (ref "H") (pin "B2") (pinfunction "P_B2") (pintype "passive"))
    )
    (net (code "36") (name "B_DRIVE_STATUS_ER") (class "Default")
      (node (ref "E40") (pin "3") (pinfunction "O_3") (pintype "output"))
      (node (ref "E53") (pin "3") (pinfunction "I1_3") (pintype "input"))
    )
    (net (code "37") (name "B_IO_PAUSE") (class "Default")
      (node (ref "E34") (pin "3") (pinfunction "I1_3") (pintype "input"))
      (node (ref "E35") (pin "14") (pinfunction "O_14") (pintype "output"))
      (node (ref "E51") (pin "3") (pinfunction "I1_3") (pintype "input"))
    )
    (net (code "38") (name "CLR_ALL") (class "Default")
      (node (ref "E19") (pin "8") (pinfunction "I0_8") (pintype "input"))
      (node (ref "E26") (pin "10") (pinfunction "I7_10") (pintype "input"))
      (node (ref "E26") (pin "9") (pinfunction "I8_9") (pintype "input"))
      (node (ref "E33") (pin "4") (pinfunction "I0_4") (pintype "input"))
      (node (ref "E33") (pin "5") (pinfunction "I1_5") (pintype "input"))
      (node (ref "E33") (pin "8") (pinfunction "O_8") (pintype "output"))
      (node (ref "E34") (pin "11") (pinfunction "I0_11") (pintype "input"))
      (node (ref "E34") (pin "5") (pinfunction "I0_5") (pintype "input"))
      (node (ref "H") (pin "D1") (pinfunction "P_D1") (pintype "passive"))
    )
    (net (code "39") (name "CRC_ERROR") (class "Default")
      (node (ref "E30") (pin "10") (pinfunction "I1_10") (pintype "input"))
      (node (ref "E49") (pin "1") (pinfunction "A0_1") (pintype "input"))
      (node (ref "E50") (pin "14") (pinfunction "QB_14") (pintype "output"))
      (node (ref "R13") (pin "1") (pinfunction "1_1") (pintype "passive"))
    )
    (net (code "40") (name "CYL_ADDRS_ER") (class "Default")
      (node (ref "E49") (pin "15") (pinfunction "A3_15") (pintype "input"))
      (node (ref "E50") (pin "10") (pinfunction "QE_10") (pintype "output"))
      (node (ref "E53") (pin "2") (pinfunction "I0_2") (pintype "input"))
    )
    (net (code "41") (name "DATA_CLK_OK") (class "Default")
      (node (ref "E39") (pin "3") (pinfunction "CLK_3") (pintype "input"))
      (node (ref "H") (pin "C1") (pinfunction "P_C1") (pintype "passive"))
    )
    (net (code "42") (name "DATA_ENABLE") (class "Default")
      (node (ref "E20") (pin "4") (pinfunction "I0_4") (pintype "input"))
      (node (ref "H") (pin "N1") (pinfunction "P_N1") (pintype "passive"))
    )
    (net (code "43") (name "DATA_RQST_LATE") (class "Default")
      (node (ref "E39") (pin "5") (pinfunction "Q_5") (pintype "output"))
      (node (ref "E49") (pin "6") (pinfunction "A1_6") (pintype "input"))
    )
    (net (code "44") (name "DATA_STATE") (class "Default")
      (node (ref "E26") (pin "4") (pinfunction "I1_4") (pintype "input"))
      (node (ref "H") (pin "L1") (pinfunction "P_L1") (pintype "passive"))
    )
    (net (code "45") (name "DB4_ENA") (class "Default")
      (node (ref "E14") (pin "8") (pinfunction "CLR_8") (pintype "input"))
      (node (ref "E26") (pin "8") (pinfunction "O_8") (pintype "output"))
      (node (ref "E6") (pin "2") (pinfunction "I5_2") (pintype "input"))
    )
    (net (code "46") (name "DB_CLK") (class "Default")
      (node (ref "E11") (pin "10") (pinfunction "I1_10") (pintype "input"))
      (node (ref "E12") (pin "5") (pinfunction "CLK_5") (pintype "input"))
      (node (ref "E14") (pin "1") (pinfunction "CLK_1") (pintype "input"))
      (node (ref "E14") (pin "6") (pinfunction "CLK_6") (pintype "input"))
      (node (ref "E7") (pin "10") (pinfunction "B_10") (pintype "input"))
      (node (ref "E7") (pin "13") (pinfunction "Q_13") (pintype "output"))
    )
    (net (code "47") (name "DB_CONT1") (class "Default")
      (node (ref "E12") (pin "12") (pinfunction "Q_12") (pintype "output"))
      (node (ref "E46") (pin "5") (pinfunction "I1_5") (pintype "input"))
    )
    (net (code "48") (name "DB_CONT2") (class "Default")
      (node (ref "E11") (pin "5") (pinfunction "I1_5") (pintype "input"))
      (node (ref "E12") (pin "9") (pinfunction "Q_9") (pintype "output"))
      (node (ref "E25") (pin "9") (pinfunction "CLK_9") (pintype "input"))
      (node (ref "E4") (pin "9") (pinfunction "CLK_9") (pintype "input"))
      (node (ref "R14") (pin "1") (pinfunction "1_1") (pintype "passive"))
    )
    (net (code "49") (name "DB_CONT3") (class "Default")
      (node (ref "E10") (pin "9") (pinfunction "CLK_9") (pintype "input"))
      (node (ref "E13") (pin "8") (pinfunction "I0_8") (pintype "input"))
      (node (ref "E14") (pin "15") (pinfunction "Q_15") (pintype "output"))
      (node (ref "E18") (pin "9") (pinfunction "CLK_9") (pintype "input"))
      (node (ref "E28") (pin "8") (pinfunction "I0_8") (pintype "input"))
    )
    (net (code "50") (name "DB_CONT4") (class "Default")
      (node (ref "E13") (pin "12") (pinfunction "I1_12") (pintype "input"))
      (node (ref "E14") (pin "11") (pinfunction "Q_11") (pintype "output"))
      (node (ref "E52") (pin "10") (pinfunction "PRE_10") (pintype "input"))
      (node (ref "H") (pin "E2") (pinfunction "P_E2") (pintype "passive"))
    )
    (net (code "51") (name "DEVICE_RK") (class "Default")
      (node (ref "E1") (pin "3") (pinfunction "O_3") (pintype "output"))
      (node (ref "E31") (pin "3") (pinfunction "I_3") (pintype "input"))
      (node (ref "E36") (pin "8") (pinfunction "I0_8") (pintype "input"))
      (node (ref "E36") (pin "9") (pinfunction "I1_9") (pintype "input"))
      (node (ref "J") (pin "A1") (pinfunction "P_A1") (pintype "passive"))
    )
    (net (code "52") (name "DONE_FLAG") (class "Default")
      (node (ref "E39") (pin "8") (pinfunction "~{Q}_8") (pintype "output"))
      (node (ref "E8") (pin "1") (pinfunction "A0_1") (pintype "input"))
    )
    (net (code "53") (name "DRIVE_STATUS_BAD") (class "Default")
      (node (ref "E45") (pin "5") (pinfunction "I1_5") (pintype "input"))
      (node (ref "J") (pin "H2") (pinfunction "P_H2") (pintype "passive"))
    )
    (net (code "54") (name "DRIVE_STATUS_ER") (class "Default")
      (node (ref "E40") (pin "2") (pinfunction "I1_2") (pintype "input"))
      (node (ref "E49") (pin "10") (pinfunction "A2_10") (pintype "input"))
      (node (ref "E50") (pin "11") (pinfunction "QD_11") (pintype "output"))
    )
    (net (code "55") (name "DRV_REVO") (class "Default")
      (node (ref "E43") (pin "5") (pinfunction "UP_5") (pintype "input"))
      (node (ref "J") (pin "K2") (pinfunction "P_K2") (pintype "passive"))
    )
    (net (code "56") (name "ENABLE_STATUS") (class "Default")
      (node (ref "E45") (pin "4") (pinfunction "I0_4") (pintype "input"))
      (node (ref "E54") (pin "6") (pinfunction "O_6") (pintype "output"))
    )
    (net (code "57") (name "ENAB_INT") (class "Default")
      (node (ref "E36") (pin "6") (pinfunction "I1_6") (pintype "input"))
      (node (ref "J") (pin "B1") (pinfunction "P_B1") (pintype "passive"))
    )
    (net (code "58") (name "ENAB_RK_DATA") (class "Default")
      (node (ref "E29") (pin "1") (pinfunction "A0_1") (pintype "input"))
      (node (ref "E31") (pin "5") (pinfunction "I_5") (pintype "input"))
      (node (ref "E33") (pin "11") (pinfunction "O_11") (pintype "output"))
    )
    (net (code "59") (name "ENAB_SEEK_DONE") (class "Default")
      (node (ref "E47") (pin "4") (pinfunction "I1_4") (pintype "input"))
      (node (ref "J") (pin "S1") (pinfunction "P_S1") (pintype "passive"))
    )
    (net (code "60") (name "GND") (class "Default")
      (node (ref "C1") (pin "2") (pinfunction "2_2") (pintype "passive"))
      (node (ref "C10") (pin "2") (pinfunction "2_2") (pintype "passive"))
      (node (ref "C11") (pin "2") (pinfunction "2_2") (pintype "passive"))
      (node (ref "C12") (pin "2") (pinfunction "2_2") (pintype "passive"))
      (node (ref "C13") (pin "2") (pinfunction "2_2") (pintype "passive"))
      (node (ref "C14") (pin "2") (pinfunction "2_2") (pintype "passive"))
      (node (ref "C15") (pin "2") (pinfunction "2_2") (pintype "passive"))
      (node (ref "C16") (pin "2") (pinfunction "2_2") (pintype "passive"))
      (node (ref "C17") (pin "2") (pinfunction "2_2") (pintype "passive"))
      (node (ref "C18") (pin "2") (pinfunction "2_2") (pintype "passive"))
      (node (ref "C19") (pin "2") (pinfunction "2_2") (pintype "passive"))
      (node (ref "C2") (pin "2") (pinfunction "2_2") (pintype "passive"))
      (node (ref "C20") (pin "2") (pinfunction "2_2") (pintype "passive"))
      (node (ref "C21") (pin "2") (pinfunction "2_2") (pintype "passive"))
      (node (ref "C22") (pin "2") (pinfunction "2_2") (pintype "passive"))
      (node (ref "C23") (pin "2") (pinfunction "2_2") (pintype "passive"))
      (node (ref "C24") (pin "2") (pinfunction "2_2") (pintype "passive"))
      (node (ref "C25") (pin "2") (pinfunction "2_2") (pintype "passive"))
      (node (ref "C26") (pin "2") (pinfunction "2_2") (pintype "passive"))
      (node (ref "C27") (pin "2") (pinfunction "2_2") (pintype "passive"))
      (node (ref "C28") (pin "2") (pinfunction "2_2") (pintype "passive"))
      (node (ref "C29") (pin "2") (pinfunction "2_2") (pintype "passive"))
      (node (ref "C3") (pin "2") (pinfunction "2_2") (pintype "passive"))
      (node (ref "C30") (pin "2") (pinfunction "2_2") (pintype "passive"))
      (node (ref "C31") (pin "2") (pinfunction "2_2") (pintype "passive"))
      (node (ref "C32") (pin "2") (pinfunction "2_2") (pintype "passive"))
      (node (ref "C33") (pin "2") (pinfunction "2_2") (pintype "passive"))
      (node (ref "C34") (pin "2") (pinfunction "2_2") (pintype "passive"))
      (node (ref "C35") (pin "2") (pinfunction "2_2") (pintype "passive"))
      (node (ref "C36") (pin "2") (pinfunction "2_2") (pintype "passive"))
      (node (ref "C37") (pin "2") (pinfunction "2_2") (pintype "passive"))
      (node (ref "C38") (pin "2") (pinfunction "2_2") (pintype "passive"))
      (node (ref "C39") (pin "2") (pinfunction "2_2") (pintype "passive"))
      (node (ref "C4") (pin "2") (pinfunction "2_2") (pintype "passive"))
      (node (ref "C40") (pin "2") (pinfunction "2_2") (pintype "passive"))
      (node (ref "C41") (pin "2") (pinfunction "2_2") (pintype "passive"))
      (node (ref "C42") (pin "2") (pinfunction "2_2") (pintype "passive"))
      (node (ref "C43") (pin "2") (pinfunction "2_2") (pintype "passive"))
      (node (ref "C44") (pin "2") (pinfunction "2_2") (pintype "passive"))
      (node (ref "C45") (pin "2") (pinfunction "2_2") (pintype "passive"))
      (node (ref "C46") (pin "2") (pinfunction "2_2") (pintype "passive"))
      (node (ref "C49") (pin "2") (pinfunction "2_2") (pintype "passive"))
      (node (ref "C5") (pin "2") (pinfunction "2_2") (pintype "passive"))
      (node (ref "C50") (pin "2") (pinfunction "2_2") (pintype "passive"))
      (node (ref "C51") (pin "2") (pinfunction "2_2") (pintype "passive"))
      (node (ref "C52") (pin "2") (pinfunction "2_2") (pintype "passive"))
      (node (ref "C53") (pin "-") (pinfunction "-_-") (pintype "passive"))
      (node (ref "C54") (pin "-") (pinfunction "-_-") (pintype "passive"))
      (node (ref "C55") (pin "-") (pinfunction "-_-") (pintype "passive"))
      (node (ref "C56") (pin "2") (pinfunction "2_2") (pintype "passive"))
      (node (ref "C6") (pin "2") (pinfunction "2_2") (pintype "passive"))
      (node (ref "C7") (pin "2") (pinfunction "2_2") (pintype "passive"))
      (node (ref "C8") (pin "2") (pinfunction "2_2") (pintype "passive"))
      (node (ref "C9") (pin "2") (pinfunction "2_2") (pintype "passive"))
      (node (ref "E12") (pin "3") (pinfunction "K_3") (pintype "input"))
      (node (ref "E15") (pin "11") (pinfunction "I0_11") (pintype "input"))
      (node (ref "E15") (pin "5") (pinfunction "I1_5") (pintype "input"))
      (node (ref "E26") (pin "1") (pinfunction "I4_1") (pintype "input"))
      (node (ref "E26") (pin "13") (pinfunction "I3_13") (pintype "input"))
      (node (ref "E29") (pin "7") (pinfunction "S1_7") (pintype "input"))
      (node (ref "E29") (pin "9") (pinfunction "S0_9") (pintype "input"))
      (node (ref "E30") (pin "5") (pinfunction "I1_5") (pintype "input"))
      (node (ref "E30") (pin "6") (pinfunction "I0_6") (pintype "input"))
      (node (ref "E33") (pin "1") (pinfunction "I0_1") (pintype "input"))
      (node (ref "E33") (pin "2") (pinfunction "I1_2") (pintype "input"))
      (node (ref "E34") (pin "2") (pinfunction "I0_2") (pintype "input"))
      (node (ref "E35") (pin "11") (pinfunction "I0_11") (pintype "input"))
      (node (ref "E35") (pin "5") (pinfunction "I1_5") (pintype "input"))
      (node (ref "E39") (pin "12") (pinfunction "D_12") (pintype "input"))
      (node (ref "E42") (pin "6") (pinfunction "I0_6") (pintype "input"))
      (node (ref "E52") (pin "12") (pinfunction "D_12") (pintype "input"))
      (node (ref "E7") (pin "9") (pinfunction "A_9") (pintype "input"))
      (node (ref "E8") (pin "10") (pinfunction "A2_10") (pintype "input"))
      (node (ref "OMNIBUS") (pin "AC2") (pinfunction "1_AC2") (pintype "bidirectional"))
      (node (ref "OMNIBUS") (pin "AF1") (pinfunction "1_AF1") (pintype "bidirectional"))
      (node (ref "OMNIBUS") (pin "AF2") (pinfunction "1_AF2") (pintype "bidirectional"))
      (node (ref "OMNIBUS") (pin "AN1") (pinfunction "1_AN1") (pintype "bidirectional"))
      (node (ref "OMNIBUS") (pin "AN2") (pinfunction "1_AN2") (pintype "bidirectional"))
      (node (ref "OMNIBUS") (pin "AT1") (pinfunction "1_AT1") (pintype "bidirectional"))
      (node (ref "OMNIBUS") (pin "AT2") (pinfunction "1_AT2") (pintype "bidirectional"))
      (node (ref "OMNIBUS") (pin "BC1") (pinfunction "1_BC1") (pintype "bidirectional"))
      (node (ref "OMNIBUS") (pin "BC2") (pinfunction "1_BC2") (pintype "bidirectional"))
      (node (ref "OMNIBUS") (pin "BF1") (pinfunction "1_BF1") (pintype "bidirectional"))
      (node (ref "OMNIBUS") (pin "BF2") (pinfunction "1_BF2") (pintype "bidirectional"))
      (node (ref "OMNIBUS") (pin "BN1") (pinfunction "1_BN1") (pintype "bidirectional"))
      (node (ref "OMNIBUS") (pin "BN2") (pinfunction "1_BN2") (pintype "bidirectional"))
      (node (ref "OMNIBUS") (pin "BT1") (pinfunction "1_BT1") (pintype "bidirectional"))
      (node (ref "OMNIBUS") (pin "BT2") (pinfunction "1_BT2") (pintype "bidirectional"))
      (node (ref "OMNIBUS") (pin "CC1") (pinfunction "1_CC1") (pintype "bidirectional"))
      (node (ref "OMNIBUS") (pin "CC2") (pinfunction "1_CC2") (pintype "bidirectional"))
      (node (ref "OMNIBUS") (pin "CF1") (pinfunction "1_CF1") (pintype "bidirectional"))
      (node (ref "OMNIBUS") (pin "CF2") (pinfunction "1_CF2") (pintype "bidirectional"))
      (node (ref "OMNIBUS") (pin "CN1") (pinfunction "1_CN1") (pintype "bidirectional"))
      (node (ref "OMNIBUS") (pin "CN2") (pinfunction "1_CN2") (pintype "bidirectional"))
      (node (ref "OMNIBUS") (pin "CT1") (pinfunction "1_CT1") (pintype "bidirectional"))
      (node (ref "OMNIBUS") (pin "CT2") (pinfunction "1_CT2") (pintype "bidirectional"))
      (node (ref "OMNIBUS") (pin "DC1") (pinfunction "1_DC1") (pintype "bidirectional"))
      (node (ref "OMNIBUS") (pin "DC2") (pinfunction "1_DC2") (pintype "bidirectional"))
      (node (ref "OMNIBUS") (pin "DF1") (pinfunction "1_DF1") (pintype "bidirectional"))
      (node (ref "OMNIBUS") (pin "DF2") (pinfunction "1_DF2") (pintype "bidirectional"))
      (node (ref "OMNIBUS") (pin "DN1") (pinfunction "1_DN1") (pintype "bidirectional"))
      (node (ref "OMNIBUS") (pin "DN2") (pinfunction "1_DN2") (pintype "bidirectional"))
      (node (ref "OMNIBUS") (pin "DT1") (pinfunction "1_DT1") (pintype "bidirectional"))
      (node (ref "OMNIBUS") (pin "DT2") (pinfunction "1_DT2") (pintype "bidirectional"))
      (node (ref "R1") (pin "1") (pinfunction "1_1") (pintype "passive"))
      (node (ref "R4") (pin "1") (pinfunction "1_1") (pintype "passive"))
    )
    (net (code "61") (name "HI_DATA_IN") (class "Default")
      (node (ref "E3") (pin "1") (pinfunction "SER_1") (pintype "input"))
      (node (ref "J") (pin "R2") (pinfunction "P_R2") (pintype "passive"))
    )
    (net (code "62") (name "HI_RD_CLK") (class "Default")
      (node (ref "E27") (pin "11") (pinfunction "I_11") (pintype "input"))
      (node (ref "E46") (pin "4") (pinfunction "I0_4") (pintype "input"))
      (node (ref "J") (pin "M1") (pinfunction "P_M1") (pintype "passive"))
    )
    (net (code "63") (name "HI_WRT_CLK") (class "Default")
      (node (ref "E11") (pin "11") (pinfunction "O_11") (pintype "output"))
      (node (ref "E3") (pin "9") (pinfunction "CK1_9") (pintype "input"))
      (node (ref "E32") (pin "9") (pinfunction "CK1_9") (pintype "input"))
      (node (ref "E5") (pin "9") (pinfunction "CK1_9") (pintype "input"))
    )
    (net (code "64") (name "IDLE") (class "Default")
      (node (ref "E20") (pin "12") (pinfunction "I0_12") (pintype "input"))
      (node (ref "E27") (pin "1") (pinfunction "I_1") (pintype "input"))
      (node (ref "E40") (pin "4") (pinfunction "I0_4") (pintype "input"))
      (node (ref "E43") (pin "14") (pinfunction "CLR_14") (pintype "input"))
      (node (ref "E47") (pin "5") (pinfunction "I2_5") (pintype "input"))
      (node (ref "E48") (pin "2") (pinfunction "I1_2") (pintype "input"))
      (node (ref "J") (pin "L2") (pinfunction "P_L2") (pintype "passive"))
    )
    (net (code "65") (name "INITIALIZE") (class "Default")
      (node (ref "E35") (pin "7") (pinfunction "I1_7") (pintype "input"))
      (node (ref "OMNIBUS") (pin "CR1") (pinfunction "1_CR1") (pintype "bidirectional"))
    )
    (net (code "66") (name "LAST_WORD_PL") (class "Default")
      (node (ref "E46") (pin "10") (pinfunction "I1_10") (pintype "input"))
      (node (ref "J") (pin "N2") (pinfunction "P_N2") (pintype "passive"))
    )
    (net (code "67") (name "LD_CMD_REG") (class "Default")
      (node (ref "E34") (pin "6") (pinfunction "I1_6") (pintype "input"))
      (node (ref "J") (pin "P1") (pinfunction "P_P1") (pintype "passive"))
    )
    (net (code "68") (name "LD_DB4") (class "Default")
      (node (ref "E11") (pin "8") (pinfunction "O_8") (pintype "output"))
      (node (ref "E17") (pin "8") (pinfunction "CK2_8") (pintype "input"))
      (node (ref "E24") (pin "8") (pinfunction "CK2_8") (pintype "input"))
      (node (ref "E9") (pin "8") (pinfunction "CK2_8") (pintype "input"))
    )
    (net (code "69") (name "LD_DB_AC") (class "Default")
      (node (ref "E21") (pin "8") (pinfunction "O_8") (pintype "output"))
      (node (ref "E26") (pin "2") (pinfunction "I5_2") (pintype "input"))
    )
    (net (code "70") (name "LD_DISK_ADDRS") (class "Default")
      (node (ref "E27") (pin "9") (pinfunction "I_9") (pintype "input"))
      (node (ref "E52") (pin "3") (pinfunction "CLK_3") (pintype "input"))
      (node (ref "J") (pin "B2") (pinfunction "P_B2") (pintype "passive"))
    )
    (net (code "71") (name "LD_RD_BUFFER") (class "Default")
      (node (ref "E13") (pin "2") (pinfunction "I0_2") (pintype "input"))
      (node (ref "E19") (pin "13") (pinfunction "O_13") (pintype "output"))
      (node (ref "E3") (pin "8") (pinfunction "CK2_8") (pintype "input"))
      (node (ref "E32") (pin "8") (pinfunction "CK2_8") (pintype "input"))
      (node (ref "E5") (pin "8") (pinfunction "CK2_8") (pintype "input"))
    )
    (net (code "72") (name "LO_MAIN_DATA") (class "Default")
      (node (ref "E9") (pin "1") (pinfunction "SER_1") (pintype "input"))
      (node (ref "H") (pin "V2") (pinfunction "P_V2") (pintype "passive"))
    )
    (net (code "73") (name "MAIN") (class "Default")
      (node (ref "E38") (pin "1") (pinfunction "CLR_1") (pintype "input"))
      (node (ref "E46") (pin "9") (pinfunction "I0_9") (pintype "input"))
      (node (ref "H") (pin "A2") (pinfunction "P_A2") (pintype "passive"))
    )
    (net (code "74") (name "MAIN_PL") (class "Default")
      (node (ref "E20") (pin "9") (pinfunction "I0_9") (pintype "input"))
      (node (ref "H") (pin "T1") (pinfunction "P_T1") (pintype "passive"))
    )
    (net (code "75") (name "MD_RD_BUFF") (class "Default")
      (node (ref "E27") (pin "4") (pinfunction "O_4") (pintype "output"))
      (node (ref "E3") (pin "6") (pinfunction "MOD_6") (pintype "input"))
      (node (ref "E32") (pin "6") (pinfunction "MOD_6") (pintype "input"))
      (node (ref "E5") (pin "6") (pinfunction "MOD_6") (pintype "input"))
      (node (ref "E51") (pin "2") (pinfunction "I0_2") (pintype "input"))
    )
    (net (code "76") (name "Net-(E1A-I0)") (class "Default")
      (node (ref "E1") (pin "4") (pinfunction "I0_4") (pintype "input"))
      (node (ref "W1W4") (pin "2") (pinfunction "2_2") (pintype "passive"))
    )
    (net (code "77") (name "Net-(E1A-I1)") (class "Default")
      (node (ref "E1") (pin "5") (pinfunction "I1_5") (pintype "input"))
      (node (ref "W2W5") (pin "2") (pinfunction "2_2") (pintype "passive"))
    )
    (net (code "78") (name "Net-(E1A-I2)") (class "Default")
      (node (ref "E1") (pin "6") (pinfunction "I2_6") (pintype "input"))
      (node (ref "W3W6") (pin "2") (pinfunction "2_2") (pintype "passive"))
    )
    (net (code "79") (name "Net-(E3A-QA)") (class "Default")
      (node (ref "E3") (pin "13") (pinfunction "QA_13") (pintype "output"))
      (node (ref "E4") (pin "3") (pinfunction "D1_3") (pintype "input"))
    )
    (net (code "80") (name "Net-(E3A-QB)") (class "Default")
      (node (ref "E3") (pin "12") (pinfunction "QB_12") (pintype "output"))
      (node (ref "E4") (pin "4") (pinfunction "D2_4") (pintype "input"))
    )
    (net (code "81") (name "Net-(E3A-QC)") (class "Default")
      (node (ref "E3") (pin "11") (pinfunction "QC_11") (pintype "output"))
      (node (ref "E4") (pin "6") (pinfunction "D3_6") (pintype "input"))
    )
    (net (code "82") (name "Net-(E3A-QD)") (class "Default")
      (node (ref "E3") (pin "10") (pinfunction "QD_10") (pintype "output"))
      (node (ref "E4") (pin "11") (pinfunction "D4_11") (pintype "input"))
      (node (ref "E5") (pin "1") (pinfunction "SER_1") (pintype "input"))
    )
    (net (code "83") (name "Net-(E4A-D5)") (class "Default")
      (node (ref "E4") (pin "13") (pinfunction "D5_13") (pintype "input"))
      (node (ref "E5") (pin "13") (pinfunction "QA_13") (pintype "output"))
    )
    (net (code "84") (name "Net-(E4A-D6)") (class "Default")
      (node (ref "E4") (pin "14") (pinfunction "D6_14") (pintype "input"))
      (node (ref "E5") (pin "12") (pinfunction "QB_12") (pintype "output"))
    )
    (net (code "85") (name "Net-(E6A-O)") (class "Default")
      (node (ref "E6") (pin "8") (pinfunction "O_8") (pintype "output"))
      (node (ref "E7") (pin "1") (pinfunction "A_1") (pintype "input"))
    )
    (net (code "86") (name "Net-(E7A-C)") (class "Default")
      (node (ref "C48") (pin "2") (pinfunction "2_2") (pintype "passive"))
      (node (ref "E7") (pin "14") (pinfunction "C_14") (pintype "input"))
    )
    (net (code "87") (name "Net-(E7A-R{slash}C)") (class "Default")
      (node (ref "C48") (pin "1") (pinfunction "1_1") (pintype "passive"))
      (node (ref "E7") (pin "15") (pinfunction "R/C_15") (pintype "input"))
      (node (ref "R7") (pin "1") (pinfunction "1_1") (pintype "passive"))
    )
    (net (code "88") (name "Net-(E7B-C)") (class "Default")
      (node (ref "C47") (pin "2") (pinfunction "2_2") (pintype "passive"))
      (node (ref "E7") (pin "6") (pinfunction "C_6") (pintype "input"))
    )
    (net (code "89") (name "Net-(E7B-R{slash}C)") (class "Default")
      (node (ref "C47") (pin "1") (pinfunction "1_1") (pintype "passive"))
      (node (ref "E7") (pin "7") (pinfunction "R/C_7") (pintype "input"))
      (node (ref "R6") (pin "1") (pinfunction "1_1") (pintype "passive"))
    )
    (net (code "90") (name "Net-(E10A-D1)") (class "Default")
      (node (ref "E10") (pin "3") (pinfunction "D1_3") (pintype "input"))
      (node (ref "E4") (pin "2") (pinfunction "Q1_2") (pintype "output"))
    )
    (net (code "91") (name "Net-(E10A-D2)") (class "Default")
      (node (ref "E10") (pin "4") (pinfunction "D2_4") (pintype "input"))
      (node (ref "E4") (pin "5") (pinfunction "Q2_5") (pintype "output"))
    )
    (net (code "92") (name "Net-(E10A-D3)") (class "Default")
      (node (ref "E10") (pin "6") (pinfunction "D3_6") (pintype "input"))
      (node (ref "E4") (pin "7") (pinfunction "Q3_7") (pintype "output"))
    )
    (net (code "93") (name "Net-(E10A-D4)") (class "Default")
      (node (ref "E10") (pin "11") (pinfunction "D4_11") (pintype "input"))
      (node (ref "E4") (pin "10") (pinfunction "Q4_10") (pintype "output"))
    )
    (net (code "94") (name "Net-(E10A-D5)") (class "Default")
      (node (ref "E10") (pin "13") (pinfunction "D5_13") (pintype "input"))
      (node (ref "E4") (pin "12") (pinfunction "Q5_12") (pintype "output"))
    )
    (net (code "95") (name "Net-(E10A-D6)") (class "Default")
      (node (ref "E10") (pin "14") (pinfunction "D6_14") (pintype "input"))
      (node (ref "E4") (pin "15") (pinfunction "Q6_15") (pintype "output"))
    )
    (net (code "96") (name "Net-(E10A-Q1)") (class "Default")
      (node (ref "E10") (pin "2") (pinfunction "Q1_2") (pintype "output"))
      (node (ref "E9") (pin "2") (pinfunction "A_2") (pintype "input"))
    )
    (net (code "97") (name "Net-(E10A-Q2)") (class "Default")
      (node (ref "E10") (pin "5") (pinfunction "Q2_5") (pintype "output"))
      (node (ref "E9") (pin "3") (pinfunction "B_3") (pintype "input"))
    )
    (net (code "98") (name "Net-(E10A-Q3)") (class "Default")
      (node (ref "E10") (pin "7") (pinfunction "Q3_7") (pintype "output"))
      (node (ref "E9") (pin "4") (pinfunction "C_4") (pintype "input"))
    )
    (net (code "99") (name "Net-(E10A-Q4)") (class "Default")
      (node (ref "E10") (pin "10") (pinfunction "Q4_10") (pintype "output"))
      (node (ref "E9") (pin "5") (pinfunction "D_5") (pintype "input"))
    )
    (net (code "100") (name "Net-(E10A-Q5)") (class "Default")
      (node (ref "E10") (pin "12") (pinfunction "Q5_12") (pintype "output"))
      (node (ref "E17") (pin "2") (pinfunction "A_2") (pintype "input"))
    )
    (net (code "101") (name "Net-(E10A-Q6)") (class "Default")
      (node (ref "E10") (pin "15") (pinfunction "Q6_15") (pintype "output"))
      (node (ref "E17") (pin "3") (pinfunction "B_3") (pintype "input"))
    )
    (net (code "102") (name "Net-(E11A-O)") (class "Default")
      (node (ref "E11") (pin "3") (pinfunction "O_3") (pintype "output"))
      (node (ref "E13") (pin "3") (pinfunction "I1_3") (pintype "input"))
    )
    (net (code "103") (name "Net-(E11B-O)") (class "Default")
      (node (ref "E11") (pin "6") (pinfunction "O_6") (pintype "output"))
      (node (ref "E19") (pin "9") (pinfunction "I1_9") (pintype "input"))
    )
    (net (code "104") (name "Net-(E12A-CL)") (class "Default")
      (node (ref "E12") (pin "2") (pinfunction "CL_2") (pintype "input"))
      (node (ref "E19") (pin "10") (pinfunction "O_10") (pintype "output"))
    )
    (net (code "105") (name "Net-(E12A-CLK)") (class "Default")
      (node (ref "E12") (pin "1") (pinfunction "CLK_1") (pintype "input"))
      (node (ref "E27") (pin "6") (pinfunction "O_6") (pintype "output"))
    )
    (net (code "106") (name "Net-(E12A-J)") (class "Default")
      (node (ref "E12") (pin "14") (pinfunction "J_14") (pintype "input"))
      (node (ref "E47") (pin "12") (pinfunction "O_12") (pintype "output"))
    )
    (net (code "107") (name "Net-(E13A-O)") (class "Default")
      (node (ref "E13") (pin "1") (pinfunction "O_1") (pintype "output"))
      (node (ref "E27") (pin "5") (pinfunction "I_5") (pintype "input"))
    )
    (net (code "108") (name "Net-(E13B-I0)") (class "Default")
      (node (ref "C49") (pin "1") (pinfunction "1_1") (pintype "passive"))
      (node (ref "E13") (pin "5") (pinfunction "I0_5") (pintype "input"))
      (node (ref "R14") (pin "2") (pinfunction "2_2") (pintype "passive"))
    )
    (net (code "109") (name "Net-(E14B-PRE)") (class "Default")
      (node (ref "E14") (pin "7") (pinfunction "PRE_7") (pintype "input"))
      (node (ref "E20") (pin "8") (pinfunction "O_8") (pintype "output"))
    )
    (net (code "110") (name "Net-(E14B-~{Q})") (class "Default")
      (node (ref "E14") (pin "10") (pinfunction "~{Q}_10") (pintype "output"))
      (node (ref "R15") (pin "1") (pinfunction "1_1") (pintype "passive"))
    )
    (net (code "111") (name "Net-(E17A-C)") (class "Default")
      (node (ref "E17") (pin "4") (pinfunction "C_4") (pintype "input"))
      (node (ref "E18") (pin "2") (pinfunction "Q1_2") (pintype "output"))
    )
    (net (code "112") (name "Net-(E17A-D)") (class "Default")
      (node (ref "E17") (pin "5") (pinfunction "D_5") (pintype "input"))
      (node (ref "E18") (pin "5") (pinfunction "Q2_5") (pintype "output"))
    )
    (net (code "113") (name "Net-(E18A-D1)") (class "Default")
      (node (ref "E18") (pin "3") (pinfunction "D1_3") (pintype "input"))
      (node (ref "E25") (pin "2") (pinfunction "Q1_2") (pintype "output"))
    )
    (net (code "114") (name "Net-(E18A-D2)") (class "Default")
      (node (ref "E18") (pin "4") (pinfunction "D2_4") (pintype "input"))
      (node (ref "E25") (pin "5") (pinfunction "Q2_5") (pintype "output"))
    )
    (net (code "115") (name "Net-(E18A-D3)") (class "Default")
      (node (ref "E18") (pin "6") (pinfunction "D3_6") (pintype "input"))
      (node (ref "E25") (pin "7") (pinfunction "Q3_7") (pintype "output"))
    )
    (net (code "116") (name "Net-(E18A-D4)") (class "Default")
      (node (ref "E18") (pin "11") (pinfunction "D4_11") (pintype "input"))
      (node (ref "E25") (pin "10") (pinfunction "Q4_10") (pintype "output"))
    )
    (net (code "117") (name "Net-(E18A-D5)") (class "Default")
      (node (ref "E18") (pin "13") (pinfunction "D5_13") (pintype "input"))
      (node (ref "E25") (pin "12") (pinfunction "Q5_12") (pintype "output"))
    )
    (net (code "118") (name "Net-(E18A-D6)") (class "Default")
      (node (ref "E18") (pin "14") (pinfunction "D6_14") (pintype "input"))
      (node (ref "E25") (pin "15") (pinfunction "Q6_15") (pintype "output"))
    )
    (net (code "119") (name "Net-(E18A-Q3)") (class "Default")
      (node (ref "E18") (pin "7") (pinfunction "Q3_7") (pintype "output"))
      (node (ref "E24") (pin "2") (pinfunction "A_2") (pintype "input"))
    )
    (net (code "120") (name "Net-(E18A-Q4)") (class "Default")
      (node (ref "E18") (pin "10") (pinfunction "Q4_10") (pintype "output"))
      (node (ref "E24") (pin "3") (pinfunction "B_3") (pintype "input"))
    )
    (net (code "121") (name "Net-(E18A-Q5)") (class "Default")
      (node (ref "E18") (pin "12") (pinfunction "Q5_12") (pintype "output"))
      (node (ref "E24") (pin "4") (pinfunction "C_4") (pintype "input"))
    )
    (net (code "122") (name "Net-(E18A-Q6)") (class "Default")
      (node (ref "E18") (pin "15") (pinfunction "Q6_15") (pintype "output"))
      (node (ref "E24") (pin "5") (pinfunction "D_5") (pintype "input"))
    )
    (net (code "123") (name "Net-(E25A-D1)") (class "Default")
      (node (ref "E25") (pin "3") (pinfunction "D1_3") (pintype "input"))
      (node (ref "E5") (pin "11") (pinfunction "QC_11") (pintype "output"))
    )
    (net (code "124") (name "Net-(E25A-D2)") (class "Default")
      (node (ref "E25") (pin "4") (pinfunction "D2_4") (pintype "input"))
      (node (ref "E32") (pin "1") (pinfunction "SER_1") (pintype "input"))
      (node (ref "E5") (pin "10") (pinfunction "QD_10") (pintype "output"))
    )
    (net (code "125") (name "Net-(E25A-D3)") (class "Default")
      (node (ref "E25") (pin "6") (pinfunction "D3_6") (pintype "input"))
      (node (ref "E32") (pin "13") (pinfunction "QA_13") (pintype "output"))
    )
    (net (code "126") (name "Net-(E25A-D4)") (class "Default")
      (node (ref "E25") (pin "11") (pinfunction "D4_11") (pintype "input"))
      (node (ref "E32") (pin "12") (pinfunction "QB_12") (pintype "output"))
    )
    (net (code "127") (name "Net-(E25A-D5)") (class "Default")
      (node (ref "E25") (pin "13") (pinfunction "D5_13") (pintype "input"))
      (node (ref "E32") (pin "11") (pinfunction "QC_11") (pintype "output"))
    )
    (net (code "128") (name "Net-(E25A-D6)") (class "Default")
      (node (ref "E25") (pin "14") (pinfunction "D6_14") (pintype "input"))
      (node (ref "E32") (pin "10") (pinfunction "QD_10") (pintype "output"))
    )
    (net (code "129") (name "Net-(E27A-O)") (class "Default")
      (node (ref "E27") (pin "2") (pinfunction "O_2") (pintype "output"))
      (node (ref "R10") (pin "1") (pinfunction "1_1") (pintype "passive"))
    )
    (net (code "130") (name "Net-(E27D-O)") (class "Default")
      (node (ref "E27") (pin "8") (pinfunction "O_8") (pintype "output"))
      (node (ref "E54") (pin "5") (pinfunction "I1_5") (pintype "input"))
    )
    (net (code "131") (name "Net-(E27F-O)") (class "Default")
      (node (ref "E27") (pin "12") (pinfunction "O_12") (pintype "output"))
      (node (ref "R8") (pin "1") (pinfunction "1_1") (pintype "passive"))
    )
    (net (code "132") (name "Net-(E28A-O)") (class "Default")
      (node (ref "E28") (pin "1") (pinfunction "O_1") (pintype "output"))
      (node (ref "E28") (pin "5") (pinfunction "I0_5") (pintype "input"))
    )
    (net (code "133") (name "Net-(E28B-I1)") (class "Default")
      (node (ref "E28") (pin "10") (pinfunction "O_10") (pintype "output"))
      (node (ref "E28") (pin "6") (pinfunction "I1_6") (pintype "input"))
    )
    (net (code "134") (name "Net-(E28B-O)") (class "Default")
      (node (ref "E28") (pin "11") (pinfunction "I0_11") (pintype "input"))
      (node (ref "E28") (pin "4") (pinfunction "O_4") (pintype "output"))
    )
    (net (code "135") (name "Net-(E28D-O)") (class "Default")
      (node (ref "E28") (pin "13") (pinfunction "O_13") (pintype "output"))
      (node (ref "E34") (pin "12") (pinfunction "I1_12") (pintype "input"))
    )
    (net (code "136") (name "Net-(E29A-A1)") (class "Default")
      (node (ref "E29") (pin "6") (pinfunction "A1_6") (pintype "input"))
      (node (ref "E44") (pin "8") (pinfunction "O_8") (pintype "output"))
    )
    (net (code "137") (name "Net-(E29A-B1)") (class "Default")
      (node (ref "E29") (pin "5") (pinfunction "B1_5") (pintype "input"))
      (node (ref "E40") (pin "8") (pinfunction "O_8") (pintype "output"))
    )
    (net (code "138") (name "Net-(E30C-O)") (class "Default")
      (node (ref "E30") (pin "14") (pinfunction "O_14") (pintype "output"))
      (node (ref "E48") (pin "1") (pinfunction "I0_1") (pintype "input"))
      (node (ref "E53") (pin "9") (pinfunction "I1_9") (pintype "input"))
    )
    (net (code "139") (name "Net-(E33C-I0)") (class "Default")
      (node (ref "E33") (pin "9") (pinfunction "I0_9") (pintype "input"))
      (node (ref "E35") (pin "2") (pinfunction "O_2") (pintype "output"))
    )
    (net (code "140") (name "Net-(E33C-I1)") (class "Default")
      (node (ref "E33") (pin "10") (pinfunction "I1_10") (pintype "input"))
      (node (ref "E41") (pin "6") (pinfunction "O_6") (pintype "output"))
    )
    (net (code "141") (name "Net-(E34B-O)") (class "Default")
      (node (ref "E34") (pin "4") (pinfunction "O_4") (pintype "output"))
      (node (ref "E48") (pin "4") (pinfunction "I0_4") (pintype "input"))
    )
    (net (code "142") (name "Net-(E34D-O)") (class "Default")
      (node (ref "E34") (pin "13") (pinfunction "O_13") (pintype "output"))
      (node (ref "E38") (pin "13") (pinfunction "CLR_13") (pintype "input"))
    )
    (net (code "143") (name "Net-(E35A-O)") (class "Default")
      (node (ref "E35") (pin "3") (pinfunction "O_3") (pintype "output"))
      (node (ref "E35") (pin "6") (pinfunction "I0_6") (pintype "input"))
    )
    (net (code "144") (name "Net-(E35D-O)") (class "Default")
      (node (ref "E35") (pin "13") (pinfunction "O_13") (pintype "output"))
      (node (ref "E38") (pin "2") (pinfunction "D_2") (pintype "input"))
    )
    (net (code "145") (name "Net-(E36A-I0)") (class "Default")
      (node (ref "E36") (pin "2") (pinfunction "I0_2") (pintype "input"))
      (node (ref "E36") (pin "5") (pinfunction "I0_5") (pintype "input"))
      (node (ref "E54") (pin "3") (pinfunction "O_3") (pintype "output"))
    )
    (net (code "146") (name "Net-(E39A-PRE)") (class "Default")
      (node (ref "E39") (pin "4") (pinfunction "PRE_4") (pintype "input"))
      (node (ref "E46") (pin "6") (pinfunction "O_6") (pintype "output"))
    )
    (net (code "147") (name "Net-(E39B-CLK)") (class "Default")
      (node (ref "E39") (pin "11") (pinfunction "CLK_11") (pintype "input"))
      (node (ref "E46") (pin "11") (pinfunction "O_11") (pintype "output"))
    )
    (net (code "148") (name "Net-(E39B-CLR)") (class "Default")
      (node (ref "E39") (pin "13") (pinfunction "CLR_13") (pintype "input"))
      (node (ref "E46") (pin "8") (pinfunction "O_8") (pintype "output"))
    )
    (net (code "149") (name "Net-(E40B-I1)") (class "Default")
      (node (ref "DL1") (pin "OUT") (pinfunction "OUT_OUT") (pintype "bidirectional"))
      (node (ref "E40") (pin "5") (pinfunction "I1_5") (pintype "input"))
      (node (ref "R16") (pin "1") (pinfunction "1_1") (pintype "passive"))
    )
    (net (code "150") (name "Net-(E40B-O)") (class "Default")
      (node (ref "E40") (pin "6") (pinfunction "O_6") (pintype "output"))
      (node (ref "E46") (pin "2") (pinfunction "I1_2") (pintype "input"))
    )
    (net (code "151") (name "Net-(E40D-I1)") (class "Default")
      (node (ref "C50") (pin "1") (pinfunction "1_1") (pintype "passive"))
      (node (ref "E40") (pin "13") (pinfunction "I1_13") (pintype "input"))
      (node (ref "R8") (pin "2") (pinfunction "2_2") (pintype "passive"))
    )
    (net (code "152") (name "Net-(E41D-I3)") (class "Default")
      (node (ref "E41") (pin "13") (pinfunction "I3_13") (pintype "input"))
      (node (ref "E45") (pin "3") (pinfunction "O_3") (pintype "output"))
    )
    (net (code "153") (name "Net-(E41D-O)") (class "Default")
      (node (ref "E41") (pin "8") (pinfunction "O_8") (pintype "output"))
      (node (ref "E48") (pin "12") (pinfunction "I0_12") (pintype "input"))
    )
    (net (code "154") (name "Net-(E45B-O)") (class "Default")
      (node (ref "E45") (pin "6") (pinfunction "O_6") (pintype "output"))
      (node (ref "R5") (pin "1") (pinfunction "1_1") (pintype "passive"))
    )
    (net (code "155") (name "Net-(E45C-O)") (class "Default")
      (node (ref "E45") (pin "8") (pinfunction "O_8") (pintype "output"))
      (node (ref "E48") (pin "5") (pinfunction "I1_5") (pintype "input"))
    )
    (net (code "156") (name "Net-(E45D-I1)") (class "Default")
      (node (ref "C52") (pin "1") (pinfunction "1_1") (pintype "passive"))
      (node (ref "E45") (pin "13") (pinfunction "I1_13") (pintype "input"))
      (node (ref "R5") (pin "2") (pinfunction "2_2") (pintype "passive"))
    )
    (net (code "157") (name "Net-(E46A-I0)") (class "Default")
      (node (ref "C51") (pin "1") (pinfunction "1_1") (pintype "passive"))
      (node (ref "E46") (pin "1") (pinfunction "I0_1") (pintype "input"))
      (node (ref "R10") (pin "2") (pinfunction "2_2") (pintype "passive"))
    )
    (net (code "158") (name "Net-(E46D-I0)") (class "Default")
      (node (ref "E46") (pin "12") (pinfunction "I0_12") (pintype "input"))
      (node (ref "E47") (pin "6") (pinfunction "O_6") (pintype "output"))
    )
    (net (code "159") (name "Net-(E47C-I1)") (class "Default")
      (node (ref "E47") (pin "10") (pinfunction "I1_10") (pintype "input"))
      (node (ref "E53") (pin "1") (pinfunction "O_1") (pintype "output"))
    )
    (net (code "160") (name "Net-(E47C-I2)") (class "Default")
      (node (ref "E47") (pin "11") (pinfunction "I2_11") (pintype "input"))
      (node (ref "E53") (pin "4") (pinfunction "O_4") (pintype "output"))
    )
    (net (code "161") (name "Net-(E47C-O)") (class "Default")
      (node (ref "E47") (pin "8") (pinfunction "O_8") (pintype "output"))
      (node (ref "E53") (pin "11") (pinfunction "I0_11") (pintype "input"))
      (node (ref "E53") (pin "8") (pinfunction "I0_8") (pintype "input"))
    )
    (net (code "162") (name "Net-(E48A-O)") (class "Default")
      (node (ref "E48") (pin "3") (pinfunction "O_3") (pintype "output"))
      (node (ref "E53") (pin "12") (pinfunction "I1_12") (pintype "input"))
    )
    (net (code "163") (name "Net-(E48C-O)") (class "Default")
      (node (ref "E48") (pin "13") (pinfunction "I1_13") (pintype "input"))
      (node (ref "E48") (pin "8") (pinfunction "O_8") (pintype "output"))
    )
    (net (code "164") (name "Net-(E51D-O)") (class "Default")
      (node (ref "E51") (pin "13") (pinfunction "O_13") (pintype "output"))
      (node (ref "E52") (pin "2") (pinfunction "D_2") (pintype "input"))
    )
    (net (code "165") (name "Net-(E52B-CLK)") (class "Default")
      (node (ref "E52") (pin "11") (pinfunction "CLK_11") (pintype "input"))
      (node (ref "E54") (pin "8") (pinfunction "O_8") (pintype "output"))
    )
    (net (code "166") (name "POWER_OK") (class "Default")
      (node (ref "E35") (pin "4") (pinfunction "I0_4") (pintype "input"))
      (node (ref "OMNIBUS") (pin "BV2") (pinfunction "1_BV2") (pintype "bidirectional"))
    )
    (net (code "167") (name "RDY_S{slash}R{slash}W_SLO") (class "Default")
      (node (ref "E47") (pin "3") (pinfunction "I0_3") (pintype "input"))
      (node (ref "J") (pin "L1") (pinfunction "P_L1") (pintype "passive"))
    )
    (net (code "168") (name "RK_DATA0") (class "Default")
      (node (ref "E16") (pin "5") (pinfunction "I_5") (pintype "input"))
      (node (ref "E9") (pin "13") (pinfunction "QA_13") (pintype "output"))
    )
    (net (code "169") (name "RK_DATA1") (class "Default")
      (node (ref "E16") (pin "3") (pinfunction "I_3") (pintype "input"))
      (node (ref "E9") (pin "12") (pinfunction "QB_12") (pintype "output"))
    )
    (net (code "170") (name "RK_DATA2") (class "Default")
      (node (ref "E16") (pin "11") (pinfunction "I_11") (pintype "input"))
      (node (ref "E9") (pin "11") (pinfunction "QC_11") (pintype "output"))
    )
    (net (code "171") (name "RK_DATA3") (class "Default")
      (node (ref "E16") (pin "9") (pinfunction "I_9") (pintype "input"))
      (node (ref "E17") (pin "1") (pinfunction "SER_1") (pintype "input"))
      (node (ref "E9") (pin "10") (pinfunction "QD_10") (pintype "output"))
    )
    (net (code "172") (name "RK_DATA4") (class "Default")
      (node (ref "E17") (pin "13") (pinfunction "QA_13") (pintype "output"))
      (node (ref "E23") (pin "9") (pinfunction "I_9") (pintype "input"))
    )
    (net (code "173") (name "RK_DATA5") (class "Default")
      (node (ref "E16") (pin "13") (pinfunction "I_13") (pintype "input"))
      (node (ref "E17") (pin "12") (pinfunction "QB_12") (pintype "output"))
    )
    (net (code "174") (name "RK_DATA6") (class "Default")
      (node (ref "E16") (pin "1") (pinfunction "I_1") (pintype "input"))
      (node (ref "E17") (pin "11") (pinfunction "QC_11") (pintype "output"))
    )
    (net (code "175") (name "RK_DATA7") (class "Default")
      (node (ref "E17") (pin "10") (pinfunction "QD_10") (pintype "output"))
      (node (ref "E23") (pin "11") (pinfunction "I_11") (pintype "input"))
      (node (ref "E24") (pin "1") (pinfunction "SER_1") (pintype "input"))
    )
    (net (code "176") (name "RK_DATA8") (class "Default")
      (node (ref "E23") (pin "1") (pinfunction "I_1") (pintype "input"))
      (node (ref "E24") (pin "13") (pinfunction "QA_13") (pintype "output"))
    )
    (net (code "177") (name "RK_DATA9") (class "Default")
      (node (ref "E23") (pin "5") (pinfunction "I_5") (pintype "input"))
      (node (ref "E24") (pin "12") (pinfunction "QB_12") (pintype "output"))
    )
    (net (code "178") (name "RK_DATA10") (class "Default")
      (node (ref "E23") (pin "3") (pinfunction "I_3") (pintype "input"))
      (node (ref "E24") (pin "11") (pinfunction "QC_11") (pintype "output"))
    )
    (net (code "179") (name "RK_DATA11") (class "Default")
      (node (ref "E23") (pin "13") (pinfunction "I_13") (pintype "input"))
      (node (ref "E24") (pin "10") (pinfunction "QD_10") (pintype "output"))
      (node (ref "H") (pin "F1") (pinfunction "P_F1") (pintype "passive"))
    )
    (net (code "180") (name "SEEK_FAIL") (class "Default")
      (node (ref "E8") (pin "15") (pinfunction "A3_15") (pintype "input"))
      (node (ref "H") (pin "U2") (pinfunction "P_U2") (pintype "passive"))
    )
    (net (code "181") (name "SET_BUSY_ER") (class "Default")
      (node (ref "E48") (pin "11") (pinfunction "O_11") (pintype "output"))
      (node (ref "E50") (pin "2") (pinfunction "A_2") (pintype "input"))
    )
    (net (code "182") (name "SET_CRC_ER") (class "Default")
      (node (ref "E50") (pin "3") (pinfunction "B_3") (pintype "input"))
      (node (ref "E51") (pin "4") (pinfunction "O_4") (pintype "output"))
    )
    (net (code "183") (name "SET_CYL_ADDRS_ER") (class "Default")
      (node (ref "E50") (pin "7") (pinfunction "E_7") (pintype "input"))
      (node (ref "E51") (pin "10") (pinfunction "O_10") (pintype "output"))
    )
    (net (code "184") (name "SET_STATUS_ER") (class "Default")
      (node (ref "E45") (pin "11") (pinfunction "O_11") (pintype "output"))
      (node (ref "E50") (pin "6") (pinfunction "D_6") (pintype "input"))
    )
    (net (code "185") (name "SET_TIME_OUT_ER") (class "Default")
      (node (ref "E43") (pin "7") (pinfunction "QD_7") (pintype "output"))
      (node (ref "E50") (pin "4") (pinfunction "C_4") (pintype "input"))
    )
    (net (code "186") (name "SHORT_TP3") (class "Default")
      (node (ref "E40") (pin "11") (pinfunction "O_11") (pintype "output"))
      (node (ref "E48") (pin "9") (pinfunction "I0_9") (pintype "input"))
    )
    (net (code "187") (name "TEST_CLK") (class "Default")
      (node (ref "E34") (pin "8") (pinfunction "I0_8") (pintype "input"))
      (node (ref "E7") (pin "5") (pinfunction "Q_5") (pintype "output"))
    )
    (net (code "188") (name "TIME_OUT_ER") (class "Default")
      (node (ref "E22") (pin "10") (pinfunction "A2_10") (pintype "input"))
      (node (ref "E50") (pin "13") (pinfunction "QC_13") (pintype "output"))
      (node (ref "E53") (pin "6") (pinfunction "I1_6") (pintype "input"))
    )
    (net (code "189") (name "TP1") (class "Default")
      (node (ref "E30") (pin "11") (pinfunction "I0_11") (pintype "input"))
      (node (ref "E30") (pin "12") (pinfunction "I1_12") (pintype "input"))
      (node (ref "OMNIBUS") (pin "CD2") (pinfunction "1_CD2") (pintype "bidirectional"))
    )
    (net (code "190") (name "TP2") (class "Default")
      (node (ref "E30") (pin "7") (pinfunction "I1_7") (pintype "input"))
      (node (ref "OMNIBUS") (pin "CE2") (pinfunction "1_CE2") (pintype "bidirectional"))
    )
    (net (code "191") (name "TP3") (class "Default")
      (node (ref "E30") (pin "4") (pinfunction "I0_4") (pintype "input"))
      (node (ref "OMNIBUS") (pin "CH2") (pinfunction "1_CH2") (pintype "bidirectional"))
    )
    (net (code "192") (name "VCC") (class "Default")
      (node (ref "C1") (pin "1") (pinfunction "1_1") (pintype "passive"))
      (node (ref "C10") (pin "1") (pinfunction "1_1") (pintype "passive"))
      (node (ref "C11") (pin "1") (pinfunction "1_1") (pintype "passive"))
      (node (ref "C12") (pin "1") (pinfunction "1_1") (pintype "passive"))
      (node (ref "C13") (pin "1") (pinfunction "1_1") (pintype "passive"))
      (node (ref "C14") (pin "1") (pinfunction "1_1") (pintype "passive"))
      (node (ref "C15") (pin "1") (pinfunction "1_1") (pintype "passive"))
      (node (ref "C16") (pin "1") (pinfunction "1_1") (pintype "passive"))
      (node (ref "C17") (pin "1") (pinfunction "1_1") (pintype "passive"))
      (node (ref "C18") (pin "1") (pinfunction "1_1") (pintype "passive"))
      (node (ref "C19") (pin "1") (pinfunction "1_1") (pintype "passive"))
      (node (ref "C2") (pin "1") (pinfunction "1_1") (pintype "passive"))
      (node (ref "C20") (pin "1") (pinfunction "1_1") (pintype "passive"))
      (node (ref "C21") (pin "1") (pinfunction "1_1") (pintype "passive"))
      (node (ref "C22") (pin "1") (pinfunction "1_1") (pintype "passive"))
      (node (ref "C23") (pin "1") (pinfunction "1_1") (pintype "passive"))
      (node (ref "C24") (pin "1") (pinfunction "1_1") (pintype "passive"))
      (node (ref "C25") (pin "1") (pinfunction "1_1") (pintype "passive"))
      (node (ref "C26") (pin "1") (pinfunction "1_1") (pintype "passive"))
      (node (ref "C27") (pin "1") (pinfunction "1_1") (pintype "passive"))
      (node (ref "C28") (pin "1") (pinfunction "1_1") (pintype "passive"))
      (node (ref "C29") (pin "1") (pinfunction "1_1") (pintype "passive"))
      (node (ref "C3") (pin "1") (pinfunction "1_1") (pintype "passive"))
      (node (ref "C30") (pin "1") (pinfunction "1_1") (pintype "passive"))
      (node (ref "C31") (pin "1") (pinfunction "1_1") (pintype "passive"))
      (node (ref "C32") (pin "1") (pinfunction "1_1") (pintype "passive"))
      (node (ref "C33") (pin "1") (pinfunction "1_1") (pintype "passive"))
      (node (ref "C34") (pin "1") (pinfunction "1_1") (pintype "passive"))
      (node (ref "C35") (pin "1") (pinfunction "1_1") (pintype "passive"))
      (node (ref "C36") (pin "1") (pinfunction "1_1") (pintype "passive"))
      (node (ref "C37") (pin "1") (pinfunction "1_1") (pintype "passive"))
      (node (ref "C38") (pin "1") (pinfunction "1_1") (pintype "passive"))
      (node (ref "C39") (pin "1") (pinfunction "1_1") (pintype "passive"))
      (node (ref "C4") (pin "1") (pinfunction "1_1") (pintype "passive"))
      (node (ref "C40") (pin "1") (pinfunction "1_1") (pintype "passive"))
      (node (ref "C41") (pin "1") (pinfunction "1_1") (pintype "passive"))
      (node (ref "C42") (pin "1") (pinfunction "1_1") (pintype "passive"))
      (node (ref "C43") (pin "1") (pinfunction "1_1") (pintype "passive"))
      (node (ref "C44") (pin "1") (pinfunction "1_1") (pintype "passive"))
      (node (ref "C45") (pin "1") (pinfunction "1_1") (pintype "passive"))
      (node (ref "C46") (pin "1") (pinfunction "1_1") (pintype "passive"))
      (node (ref "C5") (pin "1") (pinfunction "1_1") (pintype "passive"))
      (node (ref "C53") (pin "+") (pinfunction "+_+") (pintype "passive"))
      (node (ref "C54") (pin "+") (pinfunction "+_+") (pintype "passive"))
      (node (ref "C55") (pin "+") (pinfunction "+_+") (pintype "passive"))
      (node (ref "C6") (pin "1") (pinfunction "1_1") (pintype "passive"))
      (node (ref "C7") (pin "1") (pinfunction "1_1") (pintype "passive"))
      (node (ref "C8") (pin "1") (pinfunction "1_1") (pintype "passive"))
      (node (ref "C9") (pin "1") (pinfunction "1_1") (pintype "passive"))
      (node (ref "DL1") (pin "GND@1") (pinfunction "GND_GND@1") (pintype "power_in"))
      (node (ref "DL1") (pin "GND@2") (pinfunction "GND_GND@2") (pintype "power_in"))
      (node (ref "OMNIBUS") (pin "AA2") (pinfunction "1_AA2") (pintype "bidirectional"))
      (node (ref "OMNIBUS") (pin "BA2") (pinfunction "1_BA2") (pintype "bidirectional"))
      (node (ref "OMNIBUS") (pin "CA2") (pinfunction "1_CA2") (pintype "bidirectional"))
      (node (ref "R11") (pin "2") (pinfunction "2_2") (pintype "passive"))
      (node (ref "R12") (pin "2") (pinfunction "2_2") (pintype "passive"))
      (node (ref "R13") (pin "2") (pinfunction "2_2") (pintype "passive"))
      (node (ref "R16") (pin "2") (pinfunction "2_2") (pintype "passive"))
      (node (ref "R17") (pin "2") (pinfunction "2_2") (pintype "passive"))
      (node (ref "R2") (pin "2") (pinfunction "2_2") (pintype "passive"))
      (node (ref "R3") (pin "2") (pinfunction "2_2") (pintype "passive"))
      (node (ref "R6") (pin "2") (pinfunction "2_2") (pintype "passive"))
      (node (ref "R7") (pin "2") (pinfunction "2_2") (pintype "passive"))
      (node (ref "R9") (pin "2") (pinfunction "2_2") (pintype "passive"))
    )
    (net (code "193") (name "WRITE") (class "Default")
      (node (ref "E26") (pin "5") (pinfunction "I11_5") (pintype "input"))
      (node (ref "H") (pin "M2") (pinfunction "P_M2") (pintype "passive"))
    )
    (net (code "194") (name "WRT_BUFF_SHFT") (class "Default")
      (node (ref "E20") (pin "3") (pinfunction "O_3") (pintype "output"))
      (node (ref "E31") (pin "9") (pinfunction "I_9") (pintype "input"))
    )
    (net (code "195") (name "WRT_BUF_DATA") (class "Default")
      (node (ref "E21") (pin "12") (pinfunction "O_12") (pintype "output"))
      (node (ref "E54") (pin "10") (pinfunction "I1_10") (pintype "input"))
    )
    (net (code "196") (name "WRT_LOCK_ER") (class "Default")
      (node (ref "E22") (pin "15") (pinfunction "A3_15") (pintype "input"))
      (node (ref "E52") (pin "5") (pinfunction "Q_5") (pintype "output"))
      (node (ref "E53") (pin "5") (pinfunction "I0_5") (pintype "input"))
    )
    (net (code "197") (name "unconnected-(E6A-I9-Pad12)") (class "Default")
      (node (ref "E6") (pin "12") (pinfunction "I9_12") (pintype "passive"))
    )
    (net (code "198") (name "unconnected-(E6A-I10-Pad11)") (class "Default")
      (node (ref "E6") (pin "11") (pinfunction "I10_11") (pintype "passive"))
    )
    (net (code "199") (name "unconnected-(E7A-~{Q}-Pad4)") (class "Default")
      (node (ref "E7") (pin "4") (pinfunction "~{Q}_4") (pintype "output"))
    )
    (net (code "200") (name "unconnected-(E26A-I9-Pad12)") (class "Default")
      (node (ref "E26") (pin "12") (pinfunction "I9_12") (pintype "passive"))
    )
    (net (code "201") (name "unconnected-(E26A-I10-Pad11)") (class "Default")
      (node (ref "E26") (pin "11") (pinfunction "I10_11") (pintype "passive"))
    )
    (net (code "202") (name "unconnected-(E29A-A2-Pad10)") (class "Default")
      (node (ref "E29") (pin "10") (pinfunction "A2_10") (pintype "input"))
    )
    (net (code "203") (name "unconnected-(E29A-A3-Pad15)") (class "Default")
      (node (ref "E29") (pin "15") (pinfunction "A3_15") (pintype "input"))
    )
    (net (code "204") (name "unconnected-(E29A-B2-Pad11)") (class "Default")
      (node (ref "E29") (pin "11") (pinfunction "B2_11") (pintype "input"))
    )
    (net (code "205") (name "unconnected-(E29A-B3-Pad14)") (class "Default")
      (node (ref "E29") (pin "14") (pinfunction "B3_14") (pintype "input"))
    )
    (net (code "206") (name "unconnected-(E29A-F2-Pad12)") (class "Default")
      (node (ref "E29") (pin "12") (pinfunction "F2_12") (pintype "open_collector"))
    )
    (net (code "207") (name "unconnected-(E29A-F3-Pad13)") (class "Default")
      (node (ref "E29") (pin "13") (pinfunction "F3_13") (pintype "open_collector"))
    )
    (net (code "208") (name "unconnected-(E37A-0-Pad13)") (class "Default")
      (node (ref "E37") (pin "13") (pinfunction "0_13") (pintype "output"))
    )
    (net (code "209") (name "unconnected-(E37A-8-Pad6)") (class "Default")
      (node (ref "E37") (pin "6") (pinfunction "8_6") (pintype "output"))
    )
    (net (code "210") (name "unconnected-(E37A-9-Pad7)") (class "Default")
      (node (ref "E37") (pin "7") (pinfunction "9_7") (pintype "output"))
    )
    (net (code "211") (name "unconnected-(E38B-~{Q}-Pad8)") (class "Default")
      (node (ref "E38") (pin "8") (pinfunction "~{Q}_8") (pintype "output"))
    )
    (net (code "212") (name "unconnected-(E43A-A-Pad15)") (class "Default")
      (node (ref "E43") (pin "15") (pinfunction "A_15") (pintype "input"))
    )
    (net (code "213") (name "unconnected-(E43A-B-Pad1)") (class "Default")
      (node (ref "E43") (pin "1") (pinfunction "B_1") (pintype "input"))
    )
    (net (code "214") (name "unconnected-(E43A-BO-Pad13)") (class "Default")
      (node (ref "E43") (pin "13") (pinfunction "BO_13") (pintype "output"))
    )
    (net (code "215") (name "unconnected-(E43A-C-Pad10)") (class "Default")
      (node (ref "E43") (pin "10") (pinfunction "C_10") (pintype "input"))
    )
    (net (code "216") (name "unconnected-(E43A-CO-Pad12)") (class "Default")
      (node (ref "E43") (pin "12") (pinfunction "CO_12") (pintype "output"))
    )
    (net (code "217") (name "unconnected-(E43A-D-Pad9)") (class "Default")
      (node (ref "E43") (pin "9") (pinfunction "D_9") (pintype "input"))
    )
    (net (code "218") (name "unconnected-(E43A-QA-Pad3)") (class "Default")
      (node (ref "E43") (pin "3") (pinfunction "QA_3") (pintype "output"))
    )
    (net (code "219") (name "unconnected-(E43A-QB-Pad2)") (class "Default")
      (node (ref "E43") (pin "2") (pinfunction "QB_2") (pintype "output"))
    )
    (net (code "220") (name "unconnected-(E43A-QC-Pad6)") (class "Default")
      (node (ref "E43") (pin "6") (pinfunction "QC_6") (pintype "output"))
    )
    (net (code "221") (name "unconnected-(E50A-SER-Pad9)") (class "Default")
      (node (ref "E50") (pin "9") (pinfunction "SER_9") (pintype "input"))
    )
    (net (code "222") (name "unconnected-(E52B-~{Q}-Pad8)") (class "Default")
      (node (ref "E52") (pin "8") (pinfunction "~{Q}_8") (pintype "output"))
    )
    (net (code "223") (name "~{6RK1}") (class "Default")
      (node (ref "E31") (pin "11") (pinfunction "I_11") (pintype "input"))
      (node (ref "E37") (pin "12") (pinfunction "1_12") (pintype "output"))
    )
    (net (code "224") (name "~{6RK2}") (class "Default")
      (node (ref "DL1") (pin "IN") (pinfunction "IN_IN") (pintype "bidirectional"))
      (node (ref "E31") (pin "13") (pinfunction "I_13") (pintype "input"))
      (node (ref "E37") (pin "11") (pinfunction "2_11") (pintype "output"))
      (node (ref "E44") (pin "12") (pinfunction "I2_12") (pintype "input"))
      (node (ref "R17") (pin "1") (pinfunction "1_1") (pintype "passive"))
    )
    (net (code "225") (name "~{6RK3_OK}") (class "Default")
      (node (ref "E21") (pin "10") (pinfunction "O_10") (pintype "output"))
      (node (ref "H") (pin "S2") (pinfunction "P_S2") (pintype "passive"))
    )
    (net (code "226") (name "~{6RK3}") (class "Default")
      (node (ref "E19") (pin "5") (pinfunction "I0_5") (pintype "input"))
      (node (ref "E37") (pin "10") (pinfunction "3_10") (pintype "output"))
      (node (ref "E40") (pin "9") (pinfunction "I0_9") (pintype "input"))
      (node (ref "E41") (pin "9") (pinfunction "I0_9") (pintype "input"))
    )
    (net (code "227") (name "~{6RK4}") (class "Default")
      (node (ref "E37") (pin "9") (pinfunction "4_9") (pintype "output"))
      (node (ref "E41") (pin "12") (pinfunction "I2_12") (pintype "input"))
      (node (ref "E44") (pin "13") (pinfunction "I3_13") (pintype "input"))
      (node (ref "J") (pin "S2") (pinfunction "P_S2") (pintype "passive"))
    )
    (net (code "228") (name "~{6RK5}") (class "Default")
      (node (ref "E22") (pin "7") (pinfunction "S1_7") (pintype "input"))
      (node (ref "E29") (pin "2") (pinfunction "B0_2") (pintype "input"))
      (node (ref "E37") (pin "3") (pinfunction "5_3") (pintype "output"))
      (node (ref "E44") (pin "10") (pinfunction "I1_10") (pintype "input"))
      (node (ref "E49") (pin "7") (pinfunction "S1_7") (pintype "input"))
      (node (ref "E8") (pin "7") (pinfunction "S1_7") (pintype "input"))
    )
    (net (code "229") (name "~{6RK6}") (class "Default")
      (node (ref "E21") (pin "1") (pinfunction "I_1") (pintype "input"))
      (node (ref "E37") (pin "4") (pinfunction "6_4") (pintype "output"))
      (node (ref "E41") (pin "10") (pinfunction "I1_10") (pintype "input"))
      (node (ref "E44") (pin "9") (pinfunction "I0_9") (pintype "input"))
    )
    (net (code "230") (name "~{6RK7}") (class "Default")
      (node (ref "E19") (pin "2") (pinfunction "I0_2") (pintype "input"))
      (node (ref "E31") (pin "1") (pinfunction "I_1") (pintype "input"))
      (node (ref "E37") (pin "5") (pinfunction "7_5") (pintype "output"))
    )
    (net (code "231") (name "~{AC7}") (class "Default")
      (node (ref "E38") (pin "6") (pinfunction "~{Q}_6") (pintype "output"))
      (node (ref "H") (pin "B1") (pinfunction "P_B1") (pintype "passive"))
    )
    (net (code "232") (name "~{BDATA10}") (class "Default")
      (node (ref "E41") (pin "2") (pinfunction "I1_2") (pintype "input"))
      (node (ref "J") (pin "P2") (pinfunction "P_P2") (pintype "passive"))
    )
    (net (code "233") (name "~{BDATA11}") (class "Default")
      (node (ref "E44") (pin "2") (pinfunction "I1_2") (pintype "input"))
      (node (ref "E45") (pin "2") (pinfunction "I1_2") (pintype "input"))
      (node (ref "J") (pin "H1") (pinfunction "P_H1") (pintype "passive"))
    )
    (net (code "234") (name "~{BRK_DIR}") (class "Default")
      (node (ref "E20") (pin "5") (pinfunction "I1_5") (pintype "input"))
      (node (ref "H") (pin "P2") (pinfunction "P_P2") (pintype "passive"))
    )
    (net (code "235") (name "~{BTP3_OK}") (class "Default")
      (node (ref "E20") (pin "11") (pinfunction "O_11") (pintype "output"))
      (node (ref "E21") (pin "5") (pinfunction "I_5") (pintype "input"))
    )
    (net (code "236") (name "~{BTP3}") (class "Default")
      (node (ref "E19") (pin "12") (pinfunction "I1_12") (pintype "input"))
      (node (ref "E19") (pin "3") (pinfunction "I1_3") (pintype "input"))
      (node (ref "E21") (pin "4") (pinfunction "O_4") (pintype "output"))
      (node (ref "J") (pin "U1") (pinfunction "P_U1") (pintype "passive"))
    )
    (net (code "237") (name "~{B_IO_PAUSE}") (class "Default")
      (node (ref "E1") (pin "11") (pinfunction "I5_11") (pintype "input"))
      (node (ref "E34") (pin "1") (pinfunction "O_1") (pintype "output"))
    )
    (net (code "238") (name "~{C0}") (class "Default")
      (node (ref "E29") (pin "4") (pinfunction "F1_4") (pintype "open_collector"))
      (node (ref "OMNIBUS") (pin "CE1") (pinfunction "1_CE1") (pintype "bidirectional"))
    )
    (net (code "239") (name "~{C1}") (class "Default")
      (node (ref "E29") (pin "3") (pinfunction "F0_3") (pintype "open_collector"))
      (node (ref "OMNIBUS") (pin "CH1") (pinfunction "1_CH1") (pintype "bidirectional"))
    )
    (net (code "240") (name "~{CLR_ALL}") (class "Default")
      (node (ref "E12") (pin "6") (pinfunction "CL_6") (pintype "input"))
      (node (ref "E14") (pin "3") (pinfunction "CLR_3") (pintype "input"))
      (node (ref "E33") (pin "6") (pinfunction "O_6") (pintype "output"))
      (node (ref "J") (pin "U2") (pinfunction "P_U2") (pintype "passive"))
    )
    (net (code "241") (name "~{CLR_DRIVE_CMD}") (class "Default")
      (node (ref "E44") (pin "6") (pinfunction "O_6") (pintype "output"))
      (node (ref "E54") (pin "4") (pinfunction "I0_4") (pintype "input"))
      (node (ref "J") (pin "C2") (pinfunction "P_C2") (pintype "passive"))
    )
    (net (code "242") (name "~{CLR_STATUS}") (class "Default")
      (node (ref "E39") (pin "1") (pinfunction "CLR_1") (pintype "input"))
      (node (ref "E39") (pin "10") (pinfunction "PRE_10") (pintype "input"))
      (node (ref "E48") (pin "6") (pinfunction "O_6") (pintype "output"))
      (node (ref "E50") (pin "16") (pinfunction "CLR_16") (pintype "input"))
      (node (ref "E52") (pin "1") (pinfunction "CLR_1") (pintype "input"))
    )
    (net (code "243") (name "~{CLR_SYN}") (class "Default")
      (node (ref "E34") (pin "9") (pinfunction "I1_9") (pintype "input"))
      (node (ref "E52") (pin "9") (pinfunction "Q_9") (pintype "output"))
    )
    (net (code "244") (name "~{DATA0}") (class "Default")
      (node (ref "E8") (pin "3") (pinfunction "F0_3") (pintype "open_collector"))
      (node (ref "OMNIBUS") (pin "AR1") (pinfunction "1_AR1") (pintype "bidirectional"))
    )
    (net (code "245") (name "~{DATA1}") (class "Default")
      (node (ref "E8") (pin "4") (pinfunction "F1_4") (pintype "open_collector"))
      (node (ref "OMNIBUS") (pin "AS1") (pinfunction "1_AS1") (pintype "bidirectional"))
    )
    (net (code "246") (name "~{DATA2}") (class "Default")
      (node (ref "E8") (pin "12") (pinfunction "F2_12") (pintype "open_collector"))
      (node (ref "OMNIBUS") (pin "AU1") (pinfunction "1_AU1") (pintype "bidirectional"))
    )
    (net (code "247") (name "~{DATA3}") (class "Default")
      (node (ref "E8") (pin "13") (pinfunction "F3_13") (pintype "open_collector"))
      (node (ref "OMNIBUS") (pin "AV1") (pinfunction "1_AV1") (pintype "bidirectional"))
    )
    (net (code "248") (name "~{DATA4}") (class "Default")
      (node (ref "E22") (pin "3") (pinfunction "F0_3") (pintype "open_collector"))
      (node (ref "OMNIBUS") (pin "BR1") (pinfunction "1_BR1") (pintype "bidirectional"))
    )
    (net (code "249") (name "~{DATA5}") (class "Default")
      (node (ref "E22") (pin "4") (pinfunction "F1_4") (pintype "open_collector"))
      (node (ref "OMNIBUS") (pin "BS1") (pinfunction "1_BS1") (pintype "bidirectional"))
    )
    (net (code "250") (name "~{DATA6}") (class "Default")
      (node (ref "E22") (pin "12") (pinfunction "F2_12") (pintype "open_collector"))
      (node (ref "OMNIBUS") (pin "BU1") (pinfunction "1_BU1") (pintype "bidirectional"))
    )
    (net (code "251") (name "~{DATA7}") (class "Default")
      (node (ref "E22") (pin "13") (pinfunction "F3_13") (pintype "open_collector"))
      (node (ref "E35") (pin "12") (pinfunction "I1_12") (pintype "input"))
      (node (ref "OMNIBUS") (pin "BV1") (pinfunction "1_BV1") (pintype "bidirectional"))
    )
    (net (code "252") (name "~{DATA8}") (class "Default")
      (node (ref "E49") (pin "3") (pinfunction "F0_3") (pintype "open_collector"))
      (node (ref "OMNIBUS") (pin "DR1") (pinfunction "1_DR1") (pintype "bidirectional"))
    )
    (net (code "253") (name "~{DATA9}") (class "Default")
      (node (ref "E49") (pin "4") (pinfunction "F1_4") (pintype "open_collector"))
      (node (ref "OMNIBUS") (pin "DS1") (pinfunction "1_DS1") (pintype "bidirectional"))
    )
    (net (code "254") (name "~{DATA10}") (class "Default")
      (node (ref "E49") (pin "12") (pinfunction "F2_12") (pintype "open_collector"))
      (node (ref "OMNIBUS") (pin "DU1") (pinfunction "1_DU1") (pintype "bidirectional"))
    )
    (net (code "255") (name "~{DATA11}") (class "Default")
      (node (ref "E49") (pin "13") (pinfunction "F3_13") (pintype "open_collector"))
      (node (ref "OMNIBUS") (pin "DV1") (pinfunction "1_DV1") (pintype "bidirectional"))
    )
    (net (code "256") (name "~{DATA_RQST_LATE}") (class "Default")
      (node (ref "E39") (pin "6") (pinfunction "~{Q}_6") (pintype "output"))
      (node (ref "E47") (pin "9") (pinfunction "I0_9") (pintype "input"))
    )
    (net (code "257") (name "~{DATA_STATE}") (class "Default")
      (node (ref "E47") (pin "13") (pinfunction "I2_13") (pintype "input"))
      (node (ref "J") (pin "M2") (pinfunction "P_M2") (pintype "passive"))
    )
    (net (code "258") (name "~{DB_CONT1}") (class "Default")
      (node (ref "E12") (pin "13") (pinfunction "~{Q}_13") (pintype "output"))
      (node (ref "E13") (pin "6") (pinfunction "I1_6") (pintype "input"))
      (node (ref "H") (pin "V1") (pinfunction "P_V1") (pintype "passive"))
    )
    (net (code "259") (name "~{DB_CONT2}") (class "Default")
      (node (ref "E12") (pin "8") (pinfunction "~{Q}_8") (pintype "output"))
      (node (ref "E13") (pin "9") (pinfunction "I1_9") (pintype "input"))
      (node (ref "E28") (pin "3") (pinfunction "I1_3") (pintype "input"))
    )
    (net (code "260") (name "~{DB_CONT3}") (class "Default")
      (node (ref "E13") (pin "11") (pinfunction "I0_11") (pintype "input"))
      (node (ref "E14") (pin "14") (pinfunction "~{Q}_14") (pintype "output"))
    )
    (net (code "261") (name "~{DB_CONT4}") (class "Default")
      (node (ref "C56") (pin "1") (pinfunction "1_1") (pintype "passive"))
      (node (ref "E17") (pin "6") (pinfunction "MOD_6") (pintype "input"))
      (node (ref "E24") (pin "6") (pinfunction "MOD_6") (pintype "input"))
      (node (ref "E39") (pin "2") (pinfunction "D_2") (pintype "input"))
      (node (ref "E9") (pin "6") (pinfunction "MOD_6") (pintype "input"))
      (node (ref "R15") (pin "2") (pinfunction "2_2") (pintype "passive"))
    )
    (net (code "262") (name "~{DEVICE_RK}") (class "Default")
      (node (ref "E31") (pin "4") (pinfunction "O_4") (pintype "output"))
      (node (ref "E37") (pin "2") (pinfunction "D_2") (pintype "input"))
    )
    (net (code "263") (name "~{DONE_FLAG}") (class "Default")
      (node (ref "E39") (pin "9") (pinfunction "Q_9") (pintype "output"))
      (node (ref "E54") (pin "2") (pinfunction "I1_2") (pintype "input"))
    )
    (net (code "264") (name "~{DSK_CAPACITY_EX}") (class "Default")
      (node (ref "E45") (pin "12") (pinfunction "I0_12") (pintype "input"))
      (node (ref "J") (pin "K1") (pinfunction "P_K1") (pintype "passive"))
      (node (ref "R1") (pin "2") (pinfunction "2_2") (pintype "passive"))
      (node (ref "R2") (pin "1") (pinfunction "1_1") (pintype "passive"))
    )
    (net (code "265") (name "~{DSK_FILE_RDY}") (class "Default")
      (node (ref "E22") (pin "1") (pinfunction "A0_1") (pintype "input"))
      (node (ref "H") (pin "E1") (pinfunction "P_E1") (pintype "passive"))
    )
    (net (code "266") (name "~{DSK_WRT_STATUS}") (class "Default")
      (node (ref "E51") (pin "12") (pinfunction "I1_12") (pintype "input"))
      (node (ref "J") (pin "D2") (pinfunction "P_D2") (pintype "passive"))
      (node (ref "R3") (pin "1") (pinfunction "1_1") (pintype "passive"))
      (node (ref "R4") (pin "2") (pinfunction "2_2") (pintype "passive"))
    )
    (net (code "267") (name "~{ENAB_RK_DATA}") (class "Default")
      (node (ref "E22") (pin "9") (pinfunction "S0_9") (pintype "input"))
      (node (ref "E31") (pin "6") (pinfunction "O_6") (pintype "output"))
      (node (ref "E49") (pin "9") (pinfunction "S0_9") (pintype "input"))
      (node (ref "E8") (pin "9") (pinfunction "S0_9") (pintype "input"))
    )
    (net (code "268") (name "~{END_STATE}") (class "Default")
      (node (ref "E51") (pin "6") (pinfunction "I1_6") (pintype "input"))
      (node (ref "J") (pin "J2") (pinfunction "P_J2") (pintype "passive"))
    )
    (net (code "269") (name "~{ERROR_CLR}") (class "Default")
      (node (ref "E53") (pin "13") (pinfunction "O_13") (pintype "output"))
      (node (ref "J") (pin "D1") (pinfunction "P_D1") (pintype "passive"))
    )
    (net (code "270") (name "~{ERROR_FL}") (class "Default")
      (node (ref "E53") (pin "10") (pinfunction "O_10") (pintype "output"))
      (node (ref "E54") (pin "1") (pinfunction "I0_1") (pintype "input"))
    )
    (net (code "271") (name "~{HI_RD_CLK}") (class "Default")
      (node (ref "E11") (pin "12") (pinfunction "I0_12") (pintype "input"))
      (node (ref "E27") (pin "10") (pinfunction "O_10") (pintype "output"))
    )
    (net (code "272") (name "~{IDLE}") (class "Default")
      (node (ref "E19") (pin "6") (pinfunction "I1_6") (pintype "input"))
      (node (ref "E48") (pin "10") (pinfunction "I1_10") (pintype "input"))
      (node (ref "J") (pin "N1") (pinfunction "P_N1") (pintype "passive"))
    )
    (net (code "273") (name "~{INTERNAL_IO}") (class "Default")
      (node (ref "E36") (pin "10") (pinfunction "O_10") (pintype "open_collector"))
      (node (ref "OMNIBUS") (pin "CL1") (pinfunction "1_CL1") (pintype "bidirectional"))
    )
    (net (code "274") (name "~{INT_RQST}") (class "Default")
      (node (ref "E36") (pin "4") (pinfunction "O_4") (pintype "open_collector"))
      (node (ref "OMNIBUS") (pin "CP1") (pinfunction "1_CP1") (pintype "bidirectional"))
    )
    (net (code "275") (name "~{IO_PAUSE}") (class "Default")
      (node (ref "E35") (pin "10") (pinfunction "I1_10") (pintype "input"))
      (node (ref "OMNIBUS") (pin "CD1") (pinfunction "1_CD1") (pintype "bidirectional"))
    )
    (net (code "276") (name "~{LD_DB_AC}") (class "Default")
      (node (ref "E21") (pin "9") (pinfunction "I_9") (pintype "input"))
      (node (ref "E33") (pin "13") (pinfunction "I1_13") (pintype "input"))
      (node (ref "E40") (pin "10") (pinfunction "I1_10") (pintype "input"))
      (node (ref "E54") (pin "11") (pinfunction "O_11") (pintype "output"))
    )
    (net (code "277") (name "~{LO_MAIN_SHFT}") (class "Default")
      (node (ref "E20") (pin "1") (pinfunction "I0_1") (pintype "input"))
      (node (ref "H") (pin "P1") (pinfunction "P_P1") (pintype "passive"))
    )
    (net (code "278") (name "~{MAIN}") (class "Default")
      (node (ref "E40") (pin "1") (pinfunction "I0_1") (pintype "input"))
      (node (ref "E47") (pin "1") (pinfunction "I0_1") (pintype "input"))
      (node (ref "J") (pin "E1") (pinfunction "P_E1") (pintype "passive"))
    )
    (net (code "279") (name "~{MAK}") (class "Default")
      (node (ref "E28") (pin "12") (pinfunction "I1_12") (pintype "input"))
      (node (ref "H") (pin "J1") (pinfunction "P_J1") (pintype "passive"))
    )
    (net (code "280") (name "~{MD0}") (class "Default")
      (node (ref "E2") (pin "7") (pinfunction "I1_7") (pintype "input"))
      (node (ref "OMNIBUS") (pin "AK1") (pinfunction "1_AK1") (pintype "bidirectional"))
    )
    (net (code "281") (name "~{MD1}") (class "Default")
      (node (ref "E2") (pin "9") (pinfunction "I0_9") (pintype "input"))
      (node (ref "OMNIBUS") (pin "AL1") (pinfunction "1_AL1") (pintype "bidirectional"))
    )
    (net (code "282") (name "~{MD2}") (class "Default")
      (node (ref "E2") (pin "4") (pinfunction "I0_4") (pintype "input"))
      (node (ref "OMNIBUS") (pin "AM1") (pinfunction "1_AM1") (pintype "bidirectional"))
    )
    (net (code "283") (name "~{MD3}") (class "Default")
      (node (ref "E1") (pin "12") (pinfunction "I6_12") (pintype "input"))
      (node (ref "E2") (pin "12") (pinfunction "I1_12") (pintype "input"))
      (node (ref "OMNIBUS") (pin "AP1") (pinfunction "1_AP1") (pintype "bidirectional"))
    )
    (net (code "284") (name "~{MD4}") (class "Default")
      (node (ref "E1") (pin "10") (pinfunction "I4_10") (pintype "input"))
      (node (ref "E15") (pin "7") (pinfunction "I1_7") (pintype "input"))
      (node (ref "OMNIBUS") (pin "BK1") (pinfunction "1_BK1") (pintype "bidirectional"))
    )
    (net (code "285") (name "~{MD5}") (class "Default")
      (node (ref "E1") (pin "9") (pinfunction "I3_9") (pintype "input"))
      (node (ref "E15") (pin "9") (pinfunction "I0_9") (pintype "input"))
      (node (ref "OMNIBUS") (pin "BL1") (pinfunction "1_BL1") (pintype "bidirectional"))
    )
    (net (code "286") (name "~{MD6}") (class "Default")
      (node (ref "E15") (pin "4") (pinfunction "I0_4") (pintype "input"))
      (node (ref "OMNIBUS") (pin "BM1") (pinfunction "1_BM1") (pintype "bidirectional"))
      (node (ref "W2W5") (pin "1") (pinfunction "1_1") (pintype "passive"))
    )
    (net (code "287") (name "~{MD7}") (class "Default")
      (node (ref "E15") (pin "12") (pinfunction "I1_12") (pintype "input"))
      (node (ref "OMNIBUS") (pin "BP1") (pinfunction "1_BP1") (pintype "bidirectional"))
      (node (ref "W1W4") (pin "3") (pinfunction "3_3") (pintype "passive"))
    )
    (net (code "288") (name "~{MD8}") (class "Default")
      (node (ref "E42") (pin "7") (pinfunction "I1_7") (pintype "input"))
      (node (ref "OMNIBUS") (pin "DK1") (pinfunction "1_DK1") (pintype "bidirectional"))
      (node (ref "W3W6") (pin "3") (pinfunction "3_3") (pintype "passive"))
    )
    (net (code "289") (name "~{MD9}") (class "Default")
      (node (ref "E42") (pin "9") (pinfunction "I0_9") (pintype "input"))
      (node (ref "OMNIBUS") (pin "DL1") (pinfunction "1_DL1") (pintype "bidirectional"))
    )
    (net (code "290") (name "~{MD10}") (class "Default")
      (node (ref "E42") (pin "4") (pinfunction "I0_4") (pintype "input"))
      (node (ref "OMNIBUS") (pin "DM1") (pinfunction "1_DM1") (pintype "bidirectional"))
    )
    (net (code "291") (name "~{MD11}") (class "Default")
      (node (ref "E42") (pin "12") (pinfunction "I1_12") (pintype "input"))
      (node (ref "OMNIBUS") (pin "DP1") (pinfunction "1_DP1") (pintype "bidirectional"))
    )
    (net (code "292") (name "~{MD_RD_BUFF}") (class "Default")
      (node (ref "E15") (pin "10") (pinfunction "I1_10") (pintype "input"))
      (node (ref "E15") (pin "6") (pinfunction "I0_6") (pintype "input"))
      (node (ref "E19") (pin "11") (pinfunction "I0_11") (pintype "input"))
      (node (ref "E2") (pin "10") (pinfunction "I1_10") (pintype "input"))
      (node (ref "E2") (pin "11") (pinfunction "I0_11") (pintype "input"))
      (node (ref "E2") (pin "5") (pinfunction "I1_5") (pintype "input"))
      (node (ref "E2") (pin "6") (pinfunction "I0_6") (pintype "input"))
      (node (ref "E20") (pin "6") (pinfunction "O_6") (pintype "output"))
      (node (ref "E27") (pin "3") (pinfunction "I_3") (pintype "input"))
      (node (ref "E47") (pin "2") (pinfunction "I1_2") (pintype "input"))
      (node (ref "R9") (pin "1") (pinfunction "1_1") (pintype "passive"))
    )
    (net (code "293") (name "~{MD_RK}") (class "Default")
      (node (ref "E42") (pin "10") (pinfunction "I1_10") (pintype "input"))
      (node (ref "E42") (pin "11") (pinfunction "I0_11") (pintype "input"))
      (node (ref "E42") (pin "5") (pinfunction "I1_5") (pintype "input"))
      (node (ref "E51") (pin "1") (pinfunction "O_1") (pintype "output"))
      (node (ref "R11") (pin "1") (pinfunction "1_1") (pintype "passive"))
    )
    (net (code "294") (name "~{NOT_EQUAL}") (class "Default")
      (node (ref "E51") (pin "5") (pinfunction "I0_5") (pintype "input"))
      (node (ref "E51") (pin "8") (pinfunction "I0_8") (pintype "input"))
      (node (ref "J") (pin "F2") (pinfunction "P_F2") (pintype "passive"))
    )
    (net (code "295") (name "~{RDY_S{slash}R{slash}W}") (class "Default")
      (node (ref "E8") (pin "6") (pinfunction "A1_6") (pintype "input"))
      (node (ref "H") (pin "U1") (pinfunction "P_U1") (pintype "passive"))
    )
    (net (code "296") (name "~{RD_BRK}") (class "Default")
      (node (ref "E28") (pin "9") (pinfunction "I1_9") (pintype "input"))
      (node (ref "H") (pin "L2") (pinfunction "P_L2") (pintype "passive"))
    )
    (net (code "297") (name "~{RK_DATA0}") (class "Default")
      (node (ref "E16") (pin "6") (pinfunction "O_6") (pintype "output"))
      (node (ref "E8") (pin "2") (pinfunction "B0_2") (pintype "input"))
    )
    (net (code "298") (name "~{RK_DATA1}") (class "Default")
      (node (ref "E16") (pin "4") (pinfunction "O_4") (pintype "output"))
      (node (ref "E8") (pin "5") (pinfunction "B1_5") (pintype "input"))
    )
    (net (code "299") (name "~{RK_DATA2}") (class "Default")
      (node (ref "E16") (pin "10") (pinfunction "O_10") (pintype "output"))
      (node (ref "E8") (pin "11") (pinfunction "B2_11") (pintype "input"))
    )
    (net (code "300") (name "~{RK_DATA3}") (class "Default")
      (node (ref "E16") (pin "8") (pinfunction "O_8") (pintype "output"))
      (node (ref "E8") (pin "14") (pinfunction "B3_14") (pintype "input"))
    )
    (net (code "301") (name "~{RK_DATA4}") (class "Default")
      (node (ref "E22") (pin "2") (pinfunction "B0_2") (pintype "input"))
      (node (ref "E23") (pin "8") (pinfunction "O_8") (pintype "output"))
    )
    (net (code "302") (name "~{RK_DATA5}") (class "Default")
      (node (ref "E16") (pin "12") (pinfunction "O_12") (pintype "output"))
      (node (ref "E22") (pin "5") (pinfunction "B1_5") (pintype "input"))
    )
    (net (code "303") (name "~{RK_DATA6}") (class "Default")
      (node (ref "E16") (pin "2") (pinfunction "O_2") (pintype "output"))
      (node (ref "E22") (pin "11") (pinfunction "B2_11") (pintype "input"))
    )
    (net (code "304") (name "~{RK_DATA7}") (class "Default")
      (node (ref "E22") (pin "14") (pinfunction "B3_14") (pintype "input"))
      (node (ref "E23") (pin "10") (pinfunction "O_10") (pintype "output"))
    )
    (net (code "305") (name "~{RK_DATA8}") (class "Default")
      (node (ref "E23") (pin "2") (pinfunction "O_2") (pintype "output"))
      (node (ref "E49") (pin "2") (pinfunction "B0_2") (pintype "input"))
    )
    (net (code "306") (name "~{RK_DATA9}") (class "Default")
      (node (ref "E23") (pin "6") (pinfunction "O_6") (pintype "output"))
      (node (ref "E49") (pin "5") (pinfunction "B1_5") (pintype "input"))
    )
    (net (code "307") (name "~{RK_DATA10}") (class "Default")
      (node (ref "E23") (pin "4") (pinfunction "O_4") (pintype "output"))
      (node (ref "E49") (pin "11") (pinfunction "B2_11") (pintype "input"))
    )
    (net (code "308") (name "~{RK_DATA11}") (class "Default")
      (node (ref "E23") (pin "12") (pinfunction "O_12") (pintype "output"))
      (node (ref "E49") (pin "14") (pinfunction "B3_14") (pintype "input"))
    )
    (net (code "309") (name "~{SECTOR_SEEK}") (class "Default")
      (node (ref "E51") (pin "9") (pinfunction "I1_9") (pintype "input"))
      (node (ref "J") (pin "F1") (pinfunction "P_F1") (pintype "passive"))
    )
    (net (code "310") (name "~{SET_IDLE_PL}") (class "Default")
      (node (ref "E46") (pin "13") (pinfunction "I1_13") (pintype "input"))
      (node (ref "E46") (pin "3") (pinfunction "O_3") (pintype "output"))
      (node (ref "J") (pin "J1") (pinfunction "P_J1") (pintype "passive"))
    )
    (net (code "311") (name "~{SHFT_WRT_BUFF}") (class "Default")
      (node (ref "E20") (pin "2") (pinfunction "I1_2") (pintype "input"))
      (node (ref "H") (pin "R2") (pinfunction "P_R2") (pintype "passive"))
    )
    (net (code "312") (name "~{SKIP}") (class "Default")
      (node (ref "E36") (pin "1") (pinfunction "O_1") (pintype "open_collector"))
      (node (ref "OMNIBUS") (pin "CS1") (pinfunction "1_CS1") (pintype "bidirectional"))
    )
    (net (code "313") (name "~{TEST_CLK}") (class "Default")
      (node (ref "E7") (pin "12") (pinfunction "~{Q}_12") (pintype "output"))
      (node (ref "E7") (pin "2") (pinfunction "B_2") (pintype "input"))
    )
    (net (code "314") (name "~{TS3}") (class "Default")
      (node (ref "E35") (pin "9") (pinfunction "I0_9") (pintype "input"))
      (node (ref "OMNIBUS") (pin "CM2") (pinfunction "1_CM2") (pintype "bidirectional"))
    )
    (net (code "315") (name "~{WRT_BRK}") (class "Default")
      (node (ref "E28") (pin "2") (pinfunction "I0_2") (pintype "input"))
      (node (ref "H") (pin "H1") (pinfunction "P_H1") (pintype "passive"))
    )
    (net (code "316") (name "~{WRT_BUFF_SHFT}") (class "Default")
      (node (ref "E17") (pin "9") (pinfunction "CK1_9") (pintype "input"))
      (node (ref "E24") (pin "9") (pinfunction "CK1_9") (pintype "input"))
      (node (ref "E31") (pin "8") (pinfunction "O_8") (pintype "output"))
      (node (ref "E9") (pin "9") (pinfunction "CK1_9") (pintype "input"))
    )
    (net (code "317") (name "~{WRT_CMD}") (class "Default")
      (node (ref "E11") (pin "13") (pinfunction "I1_13") (pintype "input"))
      (node (ref "E11") (pin "2") (pinfunction "I1_2") (pintype "input"))
      (node (ref "E51") (pin "11") (pinfunction "I0_11") (pintype "input"))
      (node (ref "J") (pin "E2") (pinfunction "P_E2") (pintype "passive"))
    )
    (net (code "318") (name "~{WRT_LOCK_ER}") (class "Default")
      (node (ref "E52") (pin "6") (pinfunction "~{Q}_6") (pintype "output"))
    )
    (net (code "319") (name "~{WT_BUFF_DATA}") (class "Default")
      (node (ref "E21") (pin "13") (pinfunction "I_13") (pintype "input"))
      (node (ref "E33") (pin "12") (pinfunction "I0_12") (pintype "input"))
      (node (ref "H") (pin "D2") (pinfunction "P_D2") (pintype "passive"))
    )
  )
)
